# Sheet1.net
KiCad netlist of a schematic drawn in Altium Designer
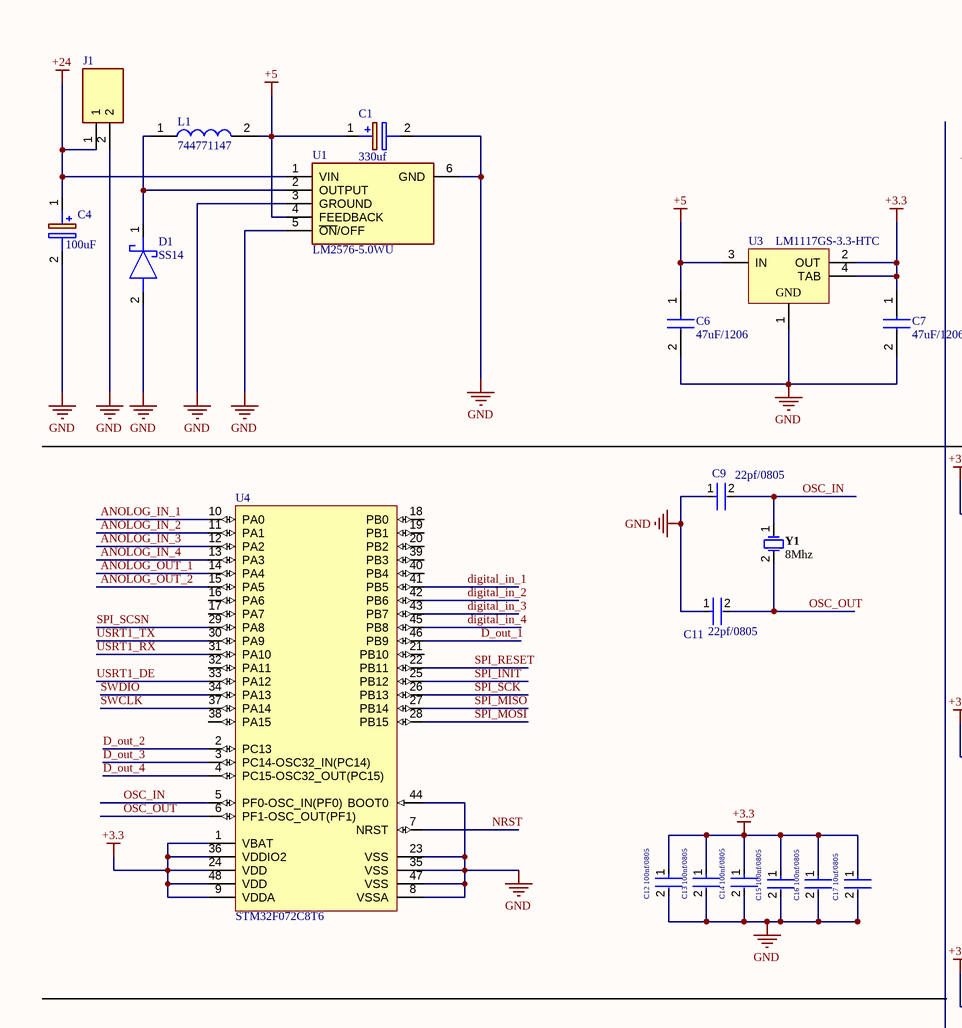
[diagram p0: Sheet1.SchDoc, top left]
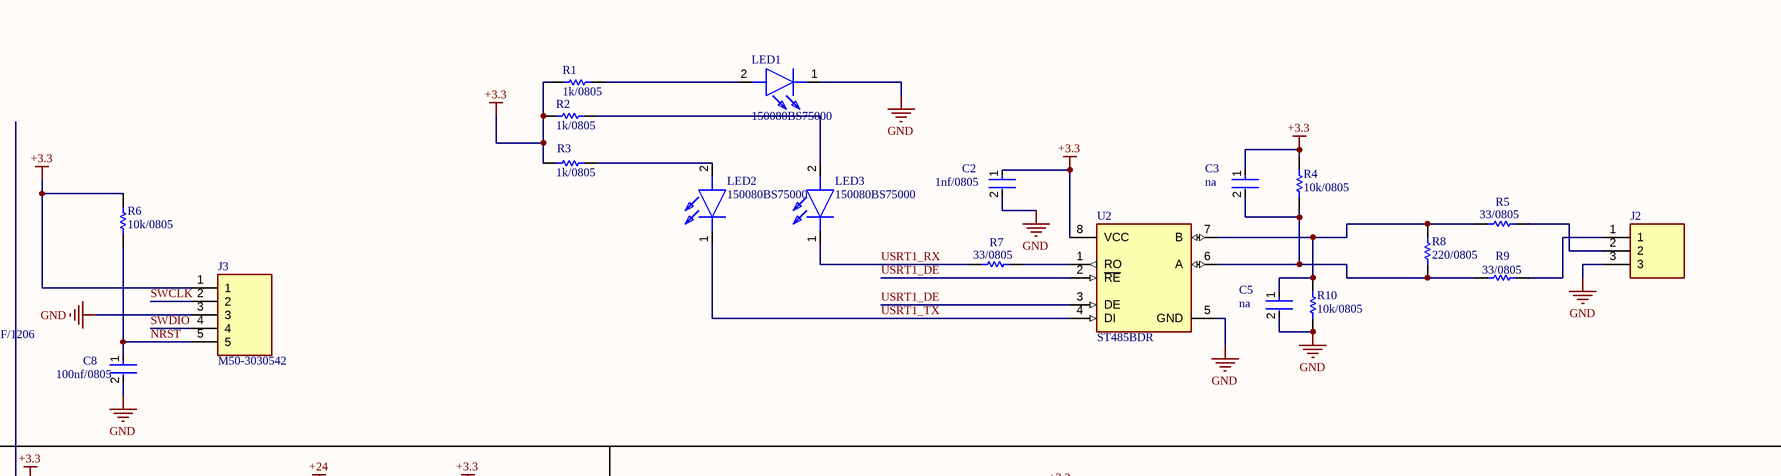
[diagram p1: Sheet1.SchDoc, top right]
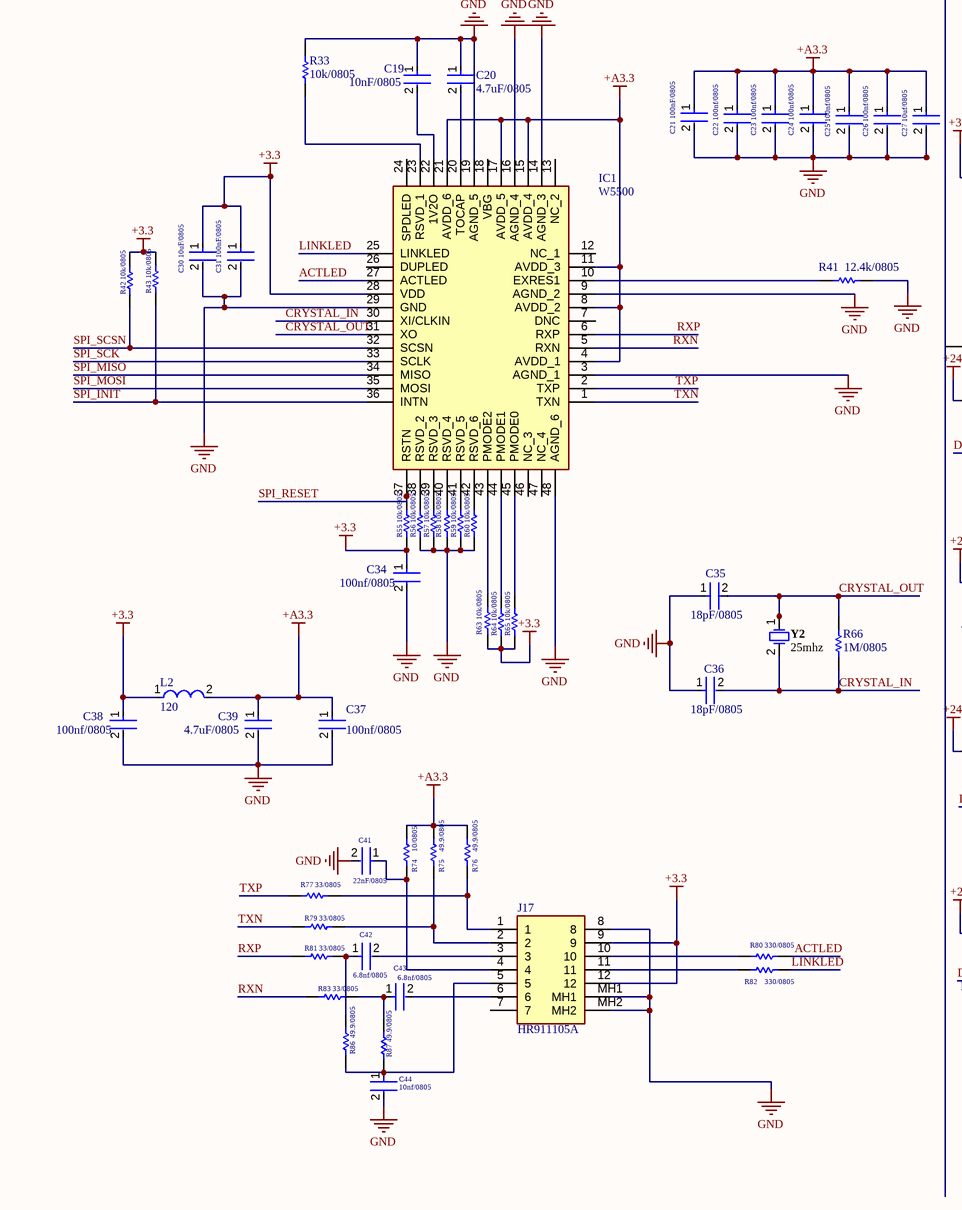
[diagram p2: Sheet1.SchDoc, bottom left]
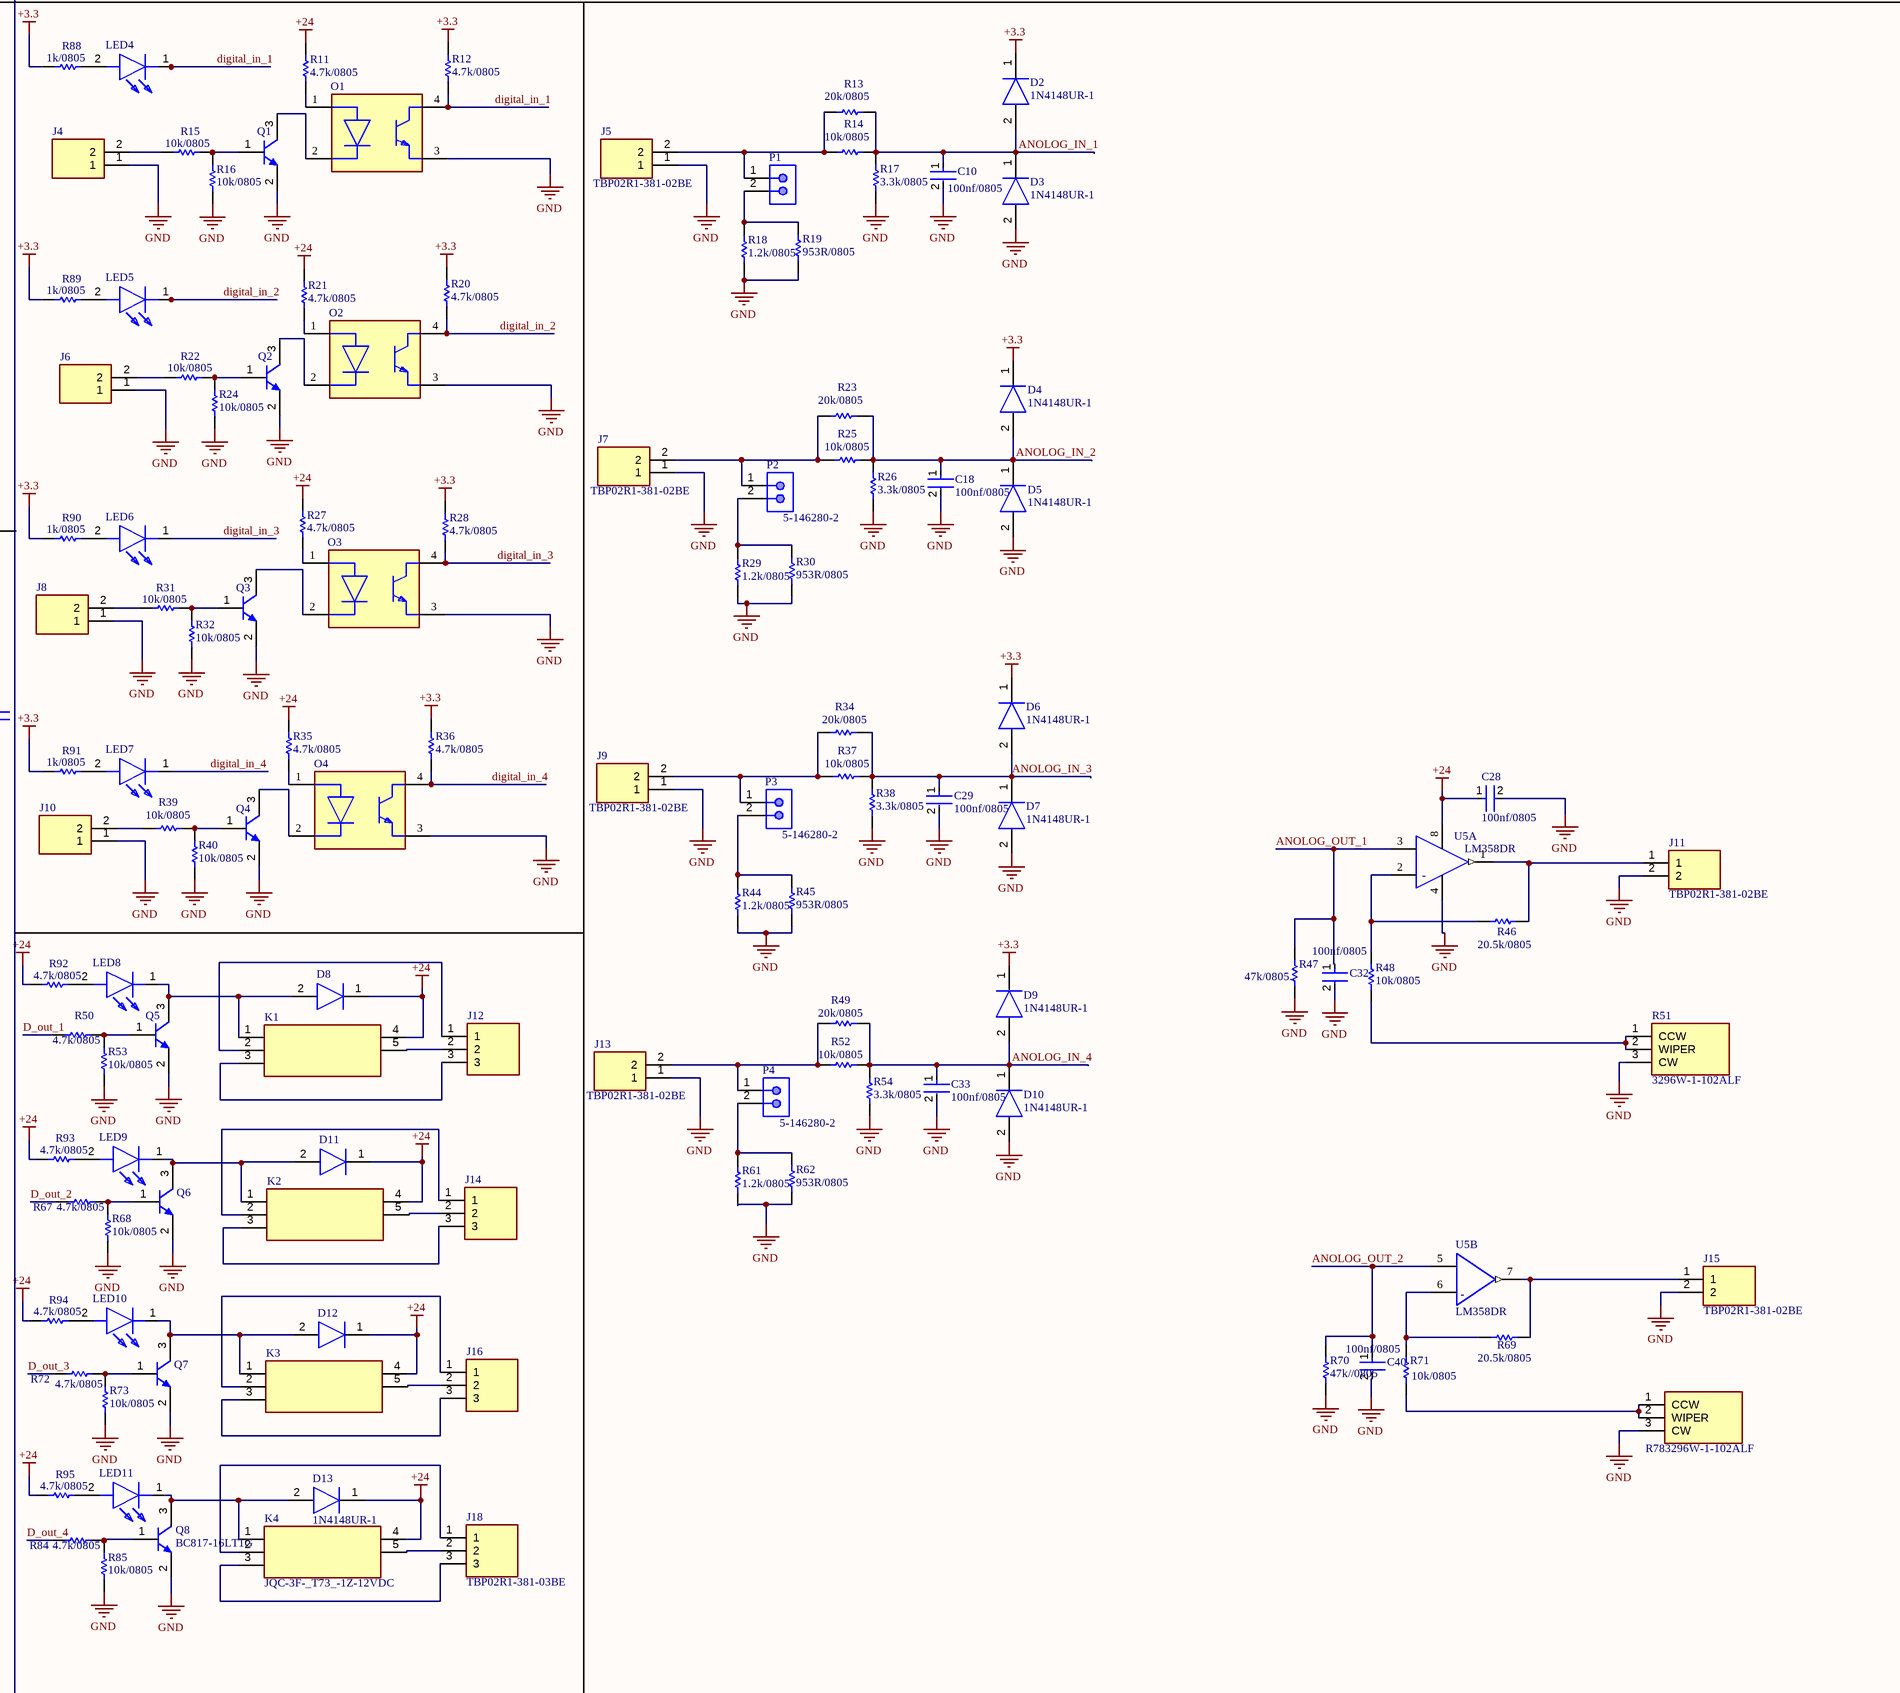
[diagram p3: Sheet1.SchDoc, bottom right]

(export (version "E")
  (design (tool "Eeschema 10.0.6"))
  (components
    (comp (ref "C1")
      (value "330uf")
      (footprint "SamacSys:CAPPRD500W60D1300H2700")
      (description "Capacitor Polarised")
      (fields
        (field (name "MANUFACTURER_PART_NUMBER") "ESH226M400AL4AA")
        (field (name "MOUSER PART NUMBER") "80-ESH226M400AL4AA")
      )
      (libsource (lib "") (part "ESH226M400AL4AA_1"))
    )
    (comp (ref "C2")
      (value "1nf/0805")
      (footprint "FP-C0805C-DG-MFG")
      (description "CAP CER 10UF 10V X5R 0805")
      (fields (field (name "TOLERANCE") "10%") (field (name "MANUFACTURER PART NUMBER") "C0805C106K8PACTU"))
      (libsource (lib "Altium Content Vault") (part "11868f565c42a9108669ba33697ecf6"))
    )
    (comp (ref "C3")
      (value "na")
      (footprint "FP-C0805C-DG-MFG")
      (description "CAP CER 10UF 10V X5R 0805")
      (fields (field (name "TOLERANCE") "10%") (field (name "MANUFACTURER PART NUMBER") "C0805C106K8PACTU"))
      (libsource (lib "Altium Content Vault") (part "11868f565c42a9108669ba33697ecf6"))
    )
    (comp (ref "C4")
      (value "100uF")
      (footprint "SamacSys:CAPPRD500W60D1300H2700")
      (description "Capacitor Polarised")
      (fields
        (field (name "MANUFACTURER_PART_NUMBER") "ESH226M400AL4AA")
        (field (name "MOUSER PART NUMBER") "80-ESH226M400AL4AA")
      )
      (libsource (lib "*") (part "ESH226M400AL4AA"))
    )
    (comp (ref "C5")
      (value "na")
      (footprint "FP-C0805C-DG-MFG")
      (description "CAP CER 10UF 10V X5R 0805")
      (fields (field (name "TOLERANCE") "10%") (field (name "MANUFACTURER PART NUMBER") "C0805C106K8PACTU"))
      (libsource (lib "Altium Content Vault") (part "11868f565c42a9108669ba33697ecf6"))
    )
    (comp (ref "C6")
      (value "47uF/1206")
      (footprint "SamacSys:CAPC3216X130N")
      (description "Capacitor")
      (fields
        (field (name "MANUFACTURER_PART_NUMBER") "CGA5H2C0G1H473J115AA")
        (field (name "MOUSER PART NUMBER") "810-CGA5H2C0G1H473J")
      )
      (libsource (lib "*") (part "CGA5H2C0G1H473J115AA"))
    )
    (comp (ref "C7")
      (value "47uF/1206")
      (footprint "SamacSys:CAPC3216X130N")
      (description "Capacitor")
      (fields
        (field (name "MANUFACTURER_PART_NUMBER") "CGA5H2C0G1H473J115AA")
        (field (name "MOUSER PART NUMBER") "810-CGA5H2C0G1H473J")
      )
      (libsource (lib "*") (part "CGA5H2C0G1H473J115AA"))
    )
    (comp (ref "C8")
      (value "100nf/0805")
      (footprint "FP-CL21-IPC_C")
      (description "CL21 Series 0805 3.3nF 25V ±5% Tolerance C0G Multilayer Ceramic Chip Capacitor")
      (fields (field (name "TOLERANCE") "5%"))
      (libsource (lib "Altium Content Vault") (part "b4654b650e69147ec39a6b967a45e02"))
    )
    (comp (ref "C9")
      (value "22pf/0805")
      (footprint "FP-CL21-IPC_A")
      (description "CL21 Series 0805 680nF 25V -20/+80% Tolerance Y5V Multilayer Ceramic Chip Capacitor")
      (fields (field (name "TOLERANCE") "80%"))
      (libsource (lib "Altium Content Vault") (part "b4654b650e69147ec39a6b967a45e02"))
    )
    (comp (ref "C10")
      (value "100nf/0805")
      (footprint "FP-CL21-IPC_C")
      (description "CL21 Series 0805 3.3nF 25V ±5% Tolerance C0G Multilayer Ceramic Chip Capacitor")
      (fields (field (name "TOLERANCE") "5%"))
      (libsource (lib "Altium Content Vault") (part "b4654b650e69147ec39a6b967a45e02"))
    )
    (comp (ref "C11")
      (value "22pf/0805")
      (footprint "FP-CL21-IPC_A")
      (description "CL21 Series 0805 680nF 25V -20/+80% Tolerance Y5V Multilayer Ceramic Chip Capacitor")
      (fields (field (name "TOLERANCE") "80%"))
      (libsource (lib "Altium Content Vault") (part "b4654b650e69147ec39a6b967a45e02"))
    )
    (comp (ref "C12")
      (value "100nf/0805")
      (footprint "FP-CL21-IPC_A")
      (description "CL21 Series 0805 680nF 25V -20/+80% Tolerance Y5V Multilayer Ceramic Chip Capacitor")
      (fields (field (name "TOLERANCE") "80%"))
      (libsource (lib "Altium Content Vault") (part "b4654b650e69147ec39a6b967a45e02"))
    )
    (comp (ref "C13")
      (value "100nf/0805")
      (footprint "FP-CL21-IPC_A")
      (description "CL21 Series 0805 680nF 25V -20/+80% Tolerance Y5V Multilayer Ceramic Chip Capacitor")
      (fields (field (name "TOLERANCE") "80%"))
      (libsource (lib "Altium Content Vault") (part "b4654b650e69147ec39a6b967a45e02"))
    )
    (comp (ref "C14")
      (value "100nf/0805")
      (footprint "FP-CL21-IPC_A")
      (description "CL21 Series 0805 680nF 25V -20/+80% Tolerance Y5V Multilayer Ceramic Chip Capacitor")
      (fields (field (name "TOLERANCE") "80%"))
      (libsource (lib "Altium Content Vault") (part "b4654b650e69147ec39a6b967a45e02"))
    )
    (comp (ref "C15")
      (value "100nf/0805")
      (footprint "FP-CL21-IPC_A")
      (description "CL21 Series 0805 680nF 25V -20/+80% Tolerance Y5V Multilayer Ceramic Chip Capacitor")
      (fields (field (name "TOLERANCE") "80%"))
      (libsource (lib "Altium Content Vault") (part "b4654b650e69147ec39a6b967a45e02"))
    )
    (comp (ref "C16")
      (value "100nf/0805")
      (footprint "FP-CL21-IPC_A")
      (description "CL21 Series 0805 680nF 25V -20/+80% Tolerance Y5V Multilayer Ceramic Chip Capacitor")
      (fields (field (name "TOLERANCE") "80%"))
      (libsource (lib "Altium Content Vault") (part "b4654b650e69147ec39a6b967a45e02"))
    )
    (comp (ref "C17")
      (value "10uf/0805")
      (footprint "FP-CL21-IPC_A")
      (description "CL21 Series 0805 680nF 25V -20/+80% Tolerance Y5V Multilayer Ceramic Chip Capacitor")
      (fields (field (name "TOLERANCE") "80%"))
      (libsource (lib "Altium Content Vault") (part "b4654b650e69147ec39a6b967a45e02"))
    )
    (comp (ref "C18")
      (value "100nf/0805")
      (footprint "FP-CL21-IPC_C")
      (description "CL21 Series 0805 3.3nF 25V ±5% Tolerance C0G Multilayer Ceramic Chip Capacitor")
      (fields (field (name "TOLERANCE") "5%"))
      (libsource (lib "Altium Content Vault") (part "b4654b650e69147ec39a6b967a45e02"))
    )
    (comp (ref "C19")
      (value "10nF/0805")
      (footprint "FP-CL21-IPC_A")
      (description "CL21 Series 0805 680nF 25V -20/+80% Tolerance Y5V Multilayer Ceramic Chip Capacitor")
      (fields (field (name "TOLERANCE") "80%"))
      (libsource (lib "Altium Content Vault") (part "b4654b650e69147ec39a6b967a45e02"))
    )
    (comp (ref "C20")
      (value "4.7uF/0805")
      (footprint "FP-CL21-IPC_A")
      (description "CL21 Series 0805 680nF 25V -20/+80% Tolerance Y5V Multilayer Ceramic Chip Capacitor")
      (fields (field (name "TOLERANCE") "80%"))
      (libsource (lib "Altium Content Vault") (part "b4654b650e69147ec39a6b967a45e02"))
    )
    (comp (ref "C21")
      (value "100nF/0805")
      (footprint "FP-CL21-IPC_A")
      (description "CL21 Series 0805 680nF 25V -20/+80% Tolerance Y5V Multilayer Ceramic Chip Capacitor")
      (fields (field (name "TOLERANCE") "80%"))
      (libsource (lib "Altium Content Vault") (part "b4654b650e69147ec39a6b967a45e02"))
    )
    (comp (ref "C22")
      (value "100nf/0805")
      (footprint "FP-CL21-IPC_A")
      (description "CL21 Series 0805 680nF 25V -20/+80% Tolerance Y5V Multilayer Ceramic Chip Capacitor")
      (fields (field (name "TOLERANCE") "80%"))
      (libsource (lib "Altium Content Vault") (part "b4654b650e69147ec39a6b967a45e02"))
    )
    (comp (ref "C23")
      (value "100nf/0805")
      (footprint "FP-CL21-IPC_A")
      (description "CL21 Series 0805 680nF 25V -20/+80% Tolerance Y5V Multilayer Ceramic Chip Capacitor")
      (fields (field (name "TOLERANCE") "80%"))
      (libsource (lib "Altium Content Vault") (part "b4654b650e69147ec39a6b967a45e02"))
    )
    (comp (ref "C24")
      (value "100nf/0805")
      (footprint "FP-CL21-IPC_A")
      (description "CL21 Series 0805 680nF 25V -20/+80% Tolerance Y5V Multilayer Ceramic Chip Capacitor")
      (fields (field (name "TOLERANCE") "80%"))
      (libsource (lib "Altium Content Vault") (part "b4654b650e69147ec39a6b967a45e02"))
    )
    (comp (ref "C25")
      (value "100nf/0805")
      (footprint "FP-CL21-IPC_A")
      (description "CL21 Series 0805 680nF 25V -20/+80% Tolerance Y5V Multilayer Ceramic Chip Capacitor")
      (fields (field (name "TOLERANCE") "80%"))
      (libsource (lib "Altium Content Vault") (part "b4654b650e69147ec39a6b967a45e02"))
    )
    (comp (ref "C26")
      (value "100nf/0805")
      (footprint "FP-CL21-IPC_A")
      (description "CL21 Series 0805 680nF 25V -20/+80% Tolerance Y5V Multilayer Ceramic Chip Capacitor")
      (fields (field (name "TOLERANCE") "80%"))
      (libsource (lib "Altium Content Vault") (part "b4654b650e69147ec39a6b967a45e02"))
    )
    (comp (ref "C27")
      (value "10uf/0805")
      (footprint "FP-CL21-IPC_A")
      (description "CL21 Series 0805 680nF 25V -20/+80% Tolerance Y5V Multilayer Ceramic Chip Capacitor")
      (fields (field (name "TOLERANCE") "80%"))
      (libsource (lib "Altium Content Vault") (part "b4654b650e69147ec39a6b967a45e02"))
    )
    (comp (ref "C28")
      (value "100nf/0805")
      (footprint "FP-CL21-IPC_C")
      (description "CL21 Series 0805 3.3nF 25V ±5% Tolerance C0G Multilayer Ceramic Chip Capacitor")
      (fields (field (name "TOLERANCE") "5%"))
      (libsource (lib "Altium Content Vault") (part "b4654b650e69147ec39a6b967a45e02"))
    )
    (comp (ref "C29")
      (value "100nf/0805")
      (footprint "FP-CL21-IPC_C")
      (description "CL21 Series 0805 3.3nF 25V ±5% Tolerance C0G Multilayer Ceramic Chip Capacitor")
      (fields (field (name "TOLERANCE") "5%"))
      (libsource (lib "Altium Content Vault") (part "b4654b650e69147ec39a6b967a45e02"))
    )
    (comp (ref "C30")
      (value "10uF/0805")
      (footprint "FP-CL21-IPC_A")
      (description "CL21 Series 0805 680nF 25V -20/+80% Tolerance Y5V Multilayer Ceramic Chip Capacitor")
      (fields (field (name "TOLERANCE") "80%"))
      (libsource (lib "Altium Content Vault") (part "b4654b650e69147ec39a6b967a45e02"))
    )
    (comp (ref "C31")
      (value "100nF/0805")
      (footprint "FP-CL21-IPC_A")
      (description "CL21 Series 0805 680nF 25V -20/+80% Tolerance Y5V Multilayer Ceramic Chip Capacitor")
      (fields (field (name "TOLERANCE") "80%"))
      (libsource (lib "Altium Content Vault") (part "b4654b650e69147ec39a6b967a45e02"))
    )
    (comp (ref "C32")
      (value "100nf/0805")
      (footprint "FP-CL21-IPC_C")
      (description "CL21 Series 0805 3.3nF 25V ±5% Tolerance C0G Multilayer Ceramic Chip Capacitor")
      (fields (field (name "TOLERANCE") "5%"))
      (libsource (lib "Altium Content Vault") (part "b4654b650e69147ec39a6b967a45e02"))
    )
    (comp (ref "C33")
      (value "100nf/0805")
      (footprint "FP-CL21-IPC_C")
      (description "CL21 Series 0805 3.3nF 25V ±5% Tolerance C0G Multilayer Ceramic Chip Capacitor")
      (fields (field (name "TOLERANCE") "5%"))
      (libsource (lib "Altium Content Vault") (part "b4654b650e69147ec39a6b967a45e02"))
    )
    (comp (ref "C34")
      (value "100nf/0805")
      (footprint "FP-CL21-IPC_C")
      (description "CL21 Series 0805 3.3nF 25V ±5% Tolerance C0G Multilayer Ceramic Chip Capacitor")
      (fields (field (name "TOLERANCE") "5%"))
      (libsource (lib "Altium Content Vault") (part "b4654b650e69147ec39a6b967a45e02"))
    )
    (comp (ref "C35")
      (value "18pF/0805")
      (footprint "FP-CL21-IPC_A")
      (description "CL21 Series 0805 680nF 25V -20/+80% Tolerance Y5V Multilayer Ceramic Chip Capacitor")
      (fields (field (name "TOLERANCE") "80%"))
      (libsource (lib "Altium Content Vault") (part "b4654b650e69147ec39a6b967a45e02"))
    )
    (comp (ref "C36")
      (value "18pF/0805")
      (footprint "FP-CL21-IPC_A")
      (description "CL21 Series 0805 680nF 25V -20/+80% Tolerance Y5V Multilayer Ceramic Chip Capacitor")
      (fields (field (name "TOLERANCE") "80%"))
      (libsource (lib "Altium Content Vault") (part "b4654b650e69147ec39a6b967a45e02"))
    )
    (comp (ref "C37")
      (value "100nf/0805")
      (footprint "FP-CL21-IPC_C")
      (description "CL21 Series 0805 3.3nF 25V ±5% Tolerance C0G Multilayer Ceramic Chip Capacitor")
      (fields (field (name "TOLERANCE") "5%"))
      (libsource (lib "Altium Content Vault") (part "b4654b650e69147ec39a6b967a45e02"))
    )
    (comp (ref "C38")
      (value "100nf/0805")
      (footprint "FP-CL21-IPC_C")
      (description "CL21 Series 0805 3.3nF 25V ±5% Tolerance C0G Multilayer Ceramic Chip Capacitor")
      (fields (field (name "TOLERANCE") "5%"))
      (libsource (lib "Altium Content Vault") (part "b4654b650e69147ec39a6b967a45e02"))
    )
    (comp (ref "C39")
      (value "4.7uF/0805")
      (footprint "FP-CL21-IPC_C")
      (description "CL21 Series 0805 3.3nF 25V ±5% Tolerance C0G Multilayer Ceramic Chip Capacitor")
      (fields (field (name "TOLERANCE") "5%"))
      (libsource (lib "Altium Content Vault") (part "b4654b650e69147ec39a6b967a45e02"))
    )
    (comp (ref "C40")
      (value "100nf/0805")
      (footprint "FP-CL21-IPC_C")
      (description "CL21 Series 0805 3.3nF 25V ±5% Tolerance C0G Multilayer Ceramic Chip Capacitor")
      (fields (field (name "TOLERANCE") "5%"))
      (libsource (lib "Altium Content Vault") (part "b4654b650e69147ec39a6b967a45e02"))
    )
    (comp (ref "C41")
      (value "22nF/0805")
      (footprint "FP-CL21-IPC_C")
      (description "CL21 Series 0805 3.3nF 25V ±5% Tolerance C0G Multilayer Ceramic Chip Capacitor")
      (fields (field (name "TOLERANCE") "5%"))
      (libsource (lib "Altium Content Vault") (part "b4654b650e69147ec39a6b967a45e02"))
    )
    (comp (ref "C42")
      (value "6.8nf/0805")
      (footprint "FP-CL21-IPC_C")
      (description "CL21 Series 0805 3.3nF 25V ±5% Tolerance C0G Multilayer Ceramic Chip Capacitor")
      (fields (field (name "TOLERANCE") "5%"))
      (libsource (lib "Altium Content Vault") (part "b4654b650e69147ec39a6b967a45e02"))
    )
    (comp (ref "C43")
      (value "6.8nf/0805")
      (footprint "FP-CL21-IPC_C")
      (description "CL21 Series 0805 3.3nF 25V ±5% Tolerance C0G Multilayer Ceramic Chip Capacitor")
      (fields (field (name "TOLERANCE") "5%"))
      (libsource (lib "Altium Content Vault") (part "b4654b650e69147ec39a6b967a45e02"))
    )
    (comp (ref "C44")
      (value "10nf/0805")
      (footprint "FP-CL21-IPC_C")
      (description "CL21 Series 0805 3.3nF 25V ±5% Tolerance C0G Multilayer Ceramic Chip Capacitor")
      (fields (field (name "TOLERANCE") "5%"))
      (libsource (lib "Altium Content Vault") (part "b4654b650e69147ec39a6b967a45e02"))
    )
    (comp (ref "D1")
      (value "SS14")
      (footprint "SamacSys:DIONM5327X242N")
      (description "Schottky Diode")
      (libsource (lib "*") (part "SS14"))
    )
    (comp (ref "D2")
      (value "1N4148UR-1")
      (footprint "SamacSys:1N4148UR1")
      (description "Diode")
      (fields (field (name "MOUSER PART NUMBER") "494-1N4148UR-1"))
      (libsource (lib "*") (part "1N4148UR-1"))
    )
    (comp (ref "D3")
      (value "1N4148UR-1")
      (footprint "SamacSys:1N4148UR1")
      (description "Diode")
      (fields (field (name "MOUSER PART NUMBER") "494-1N4148UR-1"))
      (libsource (lib "*") (part "1N4148UR-1"))
    )
    (comp (ref "D4")
      (value "1N4148UR-1")
      (footprint "SamacSys:1N4148UR1")
      (description "Diode")
      (fields (field (name "MOUSER PART NUMBER") "494-1N4148UR-1"))
      (libsource (lib "*") (part "1N4148UR-1"))
    )
    (comp (ref "D5")
      (value "1N4148UR-1")
      (footprint "SamacSys:1N4148UR1")
      (description "Diode")
      (fields (field (name "MOUSER PART NUMBER") "494-1N4148UR-1"))
      (libsource (lib "*") (part "1N4148UR-1"))
    )
    (comp (ref "D6")
      (value "1N4148UR-1")
      (footprint "SamacSys:1N4148UR1")
      (description "Diode")
      (fields (field (name "MOUSER PART NUMBER") "494-1N4148UR-1"))
      (libsource (lib "*") (part "1N4148UR-1"))
    )
    (comp (ref "D7")
      (value "1N4148UR-1")
      (footprint "SamacSys:1N4148UR1")
      (description "Diode")
      (fields (field (name "MOUSER PART NUMBER") "494-1N4148UR-1"))
      (libsource (lib "*") (part "1N4148UR-1"))
    )
    (comp (ref "D8")
      (value "~")
      (footprint "SamacSys:1N4148UR1")
      (description "Diode")
      (fields
        (field (name "MANUFACTURER_PART_NUMBER") "1N4148UR-1")
        (field (name "MOUSER PART NUMBER") "494-1N4148UR-1")
      )
      (libsource (lib "*") (part "1N4148UR-1"))
    )
    (comp (ref "D9")
      (value "1N4148UR-1")
      (footprint "SamacSys:1N4148UR1")
      (description "Diode")
      (fields (field (name "MOUSER PART NUMBER") "494-1N4148UR-1"))
      (libsource (lib "*") (part "1N4148UR-1"))
    )
    (comp (ref "D10")
      (value "1N4148UR-1")
      (footprint "SamacSys:1N4148UR1")
      (description "Diode")
      (fields (field (name "MOUSER PART NUMBER") "494-1N4148UR-1"))
      (libsource (lib "*") (part "1N4148UR-1"))
    )
    (comp (ref "D11")
      (value "~")
      (footprint "SamacSys:1N4148UR1")
      (description "Diode")
      (fields
        (field (name "MANUFACTURER_PART_NUMBER") "1N4148UR-1")
        (field (name "MOUSER PART NUMBER") "494-1N4148UR-1")
      )
      (libsource (lib "*") (part "1N4148UR-1"))
    )
    (comp (ref "D12")
      (value "~")
      (footprint "SamacSys:1N4148UR1")
      (description "Diode")
      (fields
        (field (name "MANUFACTURER_PART_NUMBER") "1N4148UR-1")
        (field (name "MOUSER PART NUMBER") "494-1N4148UR-1")
      )
      (libsource (lib "*") (part "1N4148UR-1"))
    )
    (comp (ref "D13")
      (value "1N4148UR-1")
      (footprint "SamacSys:1N4148UR1")
      (description "Diode")
      (fields (field (name "MOUSER PART NUMBER") "494-1N4148UR-1"))
      (libsource (lib "*") (part "1N4148UR-1"))
    )
    (comp (ref "IC1")
      (value "W5500")
      (footprint "SamacSys:QFP50P900X900X160-48N")
      (description "Integrated Circuit")
      (fields (field (name "MOUSER PART NUMBER") "950-W5500"))
      (libsource (lib "*") (part "W5500"))
    )
    (comp (ref "J1")
      (value "~")
      (footprint "SamacSys:TBP02R138102BE")
      (description "Connector")
      (fields
        (field (name "MANUFACTURER_PART_NUMBER") "TBP02R1-381-02BE")
        (field (name "MOUSER PART NUMBER") "490-TBP02R1-381-02BE")
      )
      (libsource (lib "") (part "TBP02R1-381-02BE_1"))
    )
    (comp (ref "J2")
      (value "~")
      (footprint "SamacSys:TBP02R138103BE")
      (description "Connector")
      (fields
        (field (name "MANUFACTURER_PART_NUMBER") "TBP02R1-381-03BE")
        (field (name "MOUSER PART NUMBER") "490-TBP02R1-381-03BE")
      )
      (libsource (lib "*") (part "TBP02R1-381-03BE"))
    )
    (comp (ref "J3")
      (value "M50-3030542")
      (footprint "SamacSys:M503030542")
      (description "Connector")
      (fields (field (name "MOUSER PART NUMBER") "855-M50-3030542"))
      (libsource (lib "*") (part "M50-3030542"))
    )
    (comp (ref "J4")
      (value "~")
      (footprint "SamacSys:TBP02R138102BE")
      (description "Connector")
      (fields
        (field (name "MANUFACTURER_PART_NUMBER") "TBP02R1-381-02BE")
        (field (name "MOUSER PART NUMBER") "490-TBP02R1-381-02BE")
      )
      (libsource (lib "*") (part "TBP02R1-381-02BE"))
    )
    (comp (ref "J5")
      (value "TBP02R1-381-02BE")
      (footprint "SamacSys:TBP02R138102BE")
      (description "Connector")
      (fields (field (name "MOUSER PART NUMBER") "490-TBP02R1-381-02BE"))
      (libsource (lib "*") (part "TBP02R1-381-02BE"))
    )
    (comp (ref "J6")
      (value "~")
      (footprint "SamacSys:TBP02R138102BE")
      (description "Connector")
      (fields
        (field (name "MANUFACTURER_PART_NUMBER") "TBP02R1-381-02BE")
        (field (name "MOUSER PART NUMBER") "490-TBP02R1-381-02BE")
      )
      (libsource (lib "*") (part "TBP02R1-381-02BE"))
    )
    (comp (ref "J7")
      (value "TBP02R1-381-02BE")
      (footprint "SamacSys:TBP02R138102BE")
      (description "Connector")
      (fields (field (name "MOUSER PART NUMBER") "490-TBP02R1-381-02BE"))
      (libsource (lib "*") (part "TBP02R1-381-02BE"))
    )
    (comp (ref "J8")
      (value "~")
      (footprint "SamacSys:TBP02R138102BE")
      (description "Connector")
      (fields
        (field (name "MANUFACTURER_PART_NUMBER") "TBP02R1-381-02BE")
        (field (name "MOUSER PART NUMBER") "490-TBP02R1-381-02BE")
      )
      (libsource (lib "*") (part "TBP02R1-381-02BE"))
    )
    (comp (ref "J9")
      (value "TBP02R1-381-02BE")
      (footprint "SamacSys:TBP02R138102BE")
      (description "Connector")
      (fields (field (name "MOUSER PART NUMBER") "490-TBP02R1-381-02BE"))
      (libsource (lib "*") (part "TBP02R1-381-02BE"))
    )
    (comp (ref "J10")
      (value "~")
      (footprint "SamacSys:TBP02R138102BE")
      (description "Connector")
      (fields
        (field (name "MANUFACTURER_PART_NUMBER") "TBP02R1-381-02BE")
        (field (name "MOUSER PART NUMBER") "490-TBP02R1-381-02BE")
      )
      (libsource (lib "*") (part "TBP02R1-381-02BE"))
    )
    (comp (ref "J11")
      (value "TBP02R1-381-02BE")
      (footprint "SamacSys:TBP02R138102BE")
      (description "Connector")
      (fields (field (name "MOUSER PART NUMBER") "490-TBP02R1-381-02BE"))
      (libsource (lib "") (part "TBP02R1-381-02BE_2"))
    )
    (comp (ref "J12")
      (value "~")
      (footprint "SamacSys:TBP02R138103BE")
      (description "Connector")
      (fields
        (field (name "MANUFACTURER_PART_NUMBER") "TBP02R1-381-03BE")
        (field (name "MOUSER PART NUMBER") "490-TBP02R1-381-03BE")
      )
      (libsource (lib "*") (part "TBP02R1-381-03BE"))
    )
    (comp (ref "J13")
      (value "TBP02R1-381-02BE")
      (footprint "SamacSys:TBP02R138102BE")
      (description "Connector")
      (fields (field (name "MOUSER PART NUMBER") "490-TBP02R1-381-02BE"))
      (libsource (lib "*") (part "TBP02R1-381-02BE"))
    )
    (comp (ref "J14")
      (value "~")
      (footprint "SamacSys:TBP02R138103BE")
      (description "Connector")
      (fields
        (field (name "MANUFACTURER_PART_NUMBER") "TBP02R1-381-03BE")
        (field (name "MOUSER PART NUMBER") "490-TBP02R1-381-03BE")
      )
      (libsource (lib "*") (part "TBP02R1-381-03BE"))
    )
    (comp (ref "J15")
      (value "TBP02R1-381-02BE")
      (footprint "SamacSys:TBP02R138102BE")
      (description "Connector")
      (fields (field (name "MOUSER PART NUMBER") "490-TBP02R1-381-02BE"))
      (libsource (lib "") (part "TBP02R1-381-02BE_2"))
    )
    (comp (ref "J16")
      (value "~")
      (footprint "SamacSys:TBP02R138103BE")
      (description "Connector")
      (fields
        (field (name "MANUFACTURER_PART_NUMBER") "TBP02R1-381-03BE")
        (field (name "MOUSER PART NUMBER") "490-TBP02R1-381-03BE")
      )
      (libsource (lib "*") (part "TBP02R1-381-03BE"))
    )
    (comp (ref "J17")
      (value "HR911105A")
      (footprint "SamacSys:HR911105A")
      (description "Connector")
      (libsource (lib "*") (part "HR911105A"))
    )
    (comp (ref "J18")
      (value "TBP02R1-381-03BE")
      (footprint "SamacSys:TBP02R138103BE")
      (description "Connector")
      (fields (field (name "MOUSER PART NUMBER") "490-TBP02R1-381-03BE"))
      (libsource (lib "*") (part "TBP02R1-381-03BE"))
    )
    (comp (ref "K1")
      (value "~")
      (footprint "SamacSys:JQC3FT731Z12VDC")
      (description "Relay or Contactor")
      (fields (field (name "MANUFACTURER_PART_NUMBER") "JQC-3F-(T73)-1Z-12VDC"))
      (libsource (lib "*") (part "JQC-3F-_T73_-1Z-12VDC"))
    )
    (comp (ref "K2")
      (value "~")
      (footprint "SamacSys:JQC3FT731Z12VDC")
      (description "Relay or Contactor")
      (fields (field (name "MANUFACTURER_PART_NUMBER") "JQC-3F-(T73)-1Z-12VDC"))
      (libsource (lib "*") (part "JQC-3F-_T73_-1Z-12VDC"))
    )
    (comp (ref "K3")
      (value "~")
      (footprint "SamacSys:JQC3FT731Z12VDC")
      (description "Relay or Contactor")
      (fields (field (name "MANUFACTURER_PART_NUMBER") "JQC-3F-(T73)-1Z-12VDC"))
      (libsource (lib "*") (part "JQC-3F-_T73_-1Z-12VDC"))
    )
    (comp (ref "K4")
      (value "JQC-3F-_T73_-1Z-12VDC")
      (footprint "SamacSys:JQC3FT731Z12VDC")
      (description "Relay or Contactor")
      (fields (field (name "MANUFACTURER_PART_NUMBER") "JQC-3F-(T73)-1Z-12VDC"))
      (libsource (lib "*") (part "JQC-3F-_T73_-1Z-12VDC"))
    )
    (comp (ref "L1")
      (value "744771147")
      (footprint "SamacSys:INDPM120120X600N")
      (description "Inductor")
      (fields (field (name "MOUSER PART NUMBER") "710-744771147"))
      (libsource (lib "*") (part "744771147"))
    )
    (comp (ref "L2")
      (value "120")
      (footprint "FP-LQH31CN_03-MFG")
      (description "Wire Wound Ferrite Inductor for General Circuits 56μH ±10% 11.57Ω 50mA 1206")
      (fields (field (name "TOLERANCE") "10%"))
      (libsource (lib "Altium Content Vault") (part "725321dda6339637d4d059423bc1c3c"))
    )
    (comp (ref "LED1")
      (value "150080BS75000")
      (footprint "SamacSys:LEDC2012X80N")
      (description "LED")
      (fields (field (name "MOUSER PART NUMBER") "710-150080BS75000"))
      (libsource (lib "*") (part "150080BS75000"))
    )
    (comp (ref "LED2")
      (value "150080BS75000")
      (footprint "SamacSys:LEDC2012X80N")
      (description "LED")
      (fields (field (name "MOUSER PART NUMBER") "710-150080BS75000"))
      (libsource (lib "*") (part "150080BS75000"))
    )
    (comp (ref "LED3")
      (value "150080BS75000")
      (footprint "SamacSys:LEDC2012X80N")
      (description "LED")
      (fields (field (name "MOUSER PART NUMBER") "710-150080BS75000"))
      (libsource (lib "*") (part "150080BS75000"))
    )
    (comp (ref "LED4")
      (value "~")
      (footprint "SamacSys:LEDC2012X80N")
      (description "LED")
      (fields
        (field (name "MANUFACTURER_PART_NUMBER") "150080BS75000")
        (field (name "MOUSER PART NUMBER") "710-150080BS75000")
      )
      (libsource (lib "*") (part "150080BS75000"))
    )
    (comp (ref "LED5")
      (value "~")
      (footprint "SamacSys:LEDC2012X80N")
      (description "LED")
      (fields
        (field (name "MANUFACTURER_PART_NUMBER") "150080BS75000")
        (field (name "MOUSER PART NUMBER") "710-150080BS75000")
      )
      (libsource (lib "*") (part "150080BS75000"))
    )
    (comp (ref "LED6")
      (value "~")
      (footprint "SamacSys:LEDC2012X80N")
      (description "LED")
      (fields
        (field (name "MANUFACTURER_PART_NUMBER") "150080BS75000")
        (field (name "MOUSER PART NUMBER") "710-150080BS75000")
      )
      (libsource (lib "*") (part "150080BS75000"))
    )
    (comp (ref "LED7")
      (value "~")
      (footprint "SamacSys:LEDC2012X80N")
      (description "LED")
      (fields
        (field (name "MANUFACTURER_PART_NUMBER") "150080BS75000")
        (field (name "MOUSER PART NUMBER") "710-150080BS75000")
      )
      (libsource (lib "*") (part "150080BS75000"))
    )
    (comp (ref "LED8")
      (value "~")
      (footprint "SamacSys:LEDC2012X80N")
      (description "LED")
      (fields
        (field (name "MANUFACTURER_PART_NUMBER") "150080BS75000")
        (field (name "MOUSER PART NUMBER") "710-150080BS75000")
      )
      (libsource (lib "*") (part "150080BS75000"))
    )
    (comp (ref "LED9")
      (value "~")
      (footprint "SamacSys:LEDC2012X80N")
      (description "LED")
      (fields
        (field (name "MANUFACTURER_PART_NUMBER") "150080BS75000")
        (field (name "MOUSER PART NUMBER") "710-150080BS75000")
      )
      (libsource (lib "*") (part "150080BS75000"))
    )
    (comp (ref "LED10")
      (value "~")
      (footprint "SamacSys:LEDC2012X80N")
      (description "LED")
      (fields
        (field (name "MANUFACTURER_PART_NUMBER") "150080BS75000")
        (field (name "MOUSER PART NUMBER") "710-150080BS75000")
      )
      (libsource (lib "*") (part "150080BS75000"))
    )
    (comp (ref "LED11")
      (value "~")
      (footprint "SamacSys:LEDC2012X80N")
      (description "LED")
      (fields
        (field (name "MANUFACTURER_PART_NUMBER") "150080BS75000")
        (field (name "MOUSER PART NUMBER") "710-150080BS75000")
      )
      (libsource (lib "*") (part "150080BS75000"))
    )
    (comp (ref "O1")
      (value "~")
      (footprint "FP-PC817XNNIP0F-MFG")
      (description "OPTOISOLATOR 5KV TRANS 4SMD")
      (libsource (lib "Altium Content Vault") (part "6470904bf6395c62928ee73e60120b8"))
    )
    (comp (ref "O2")
      (value "~")
      (footprint "FP-PC817XNNIP0F-MFG")
      (description "OPTOISOLATOR 5KV TRANS 4SMD")
      (libsource (lib "Altium Content Vault") (part "6470904bf6395c62928ee73e60120b8"))
    )
    (comp (ref "O3")
      (value "~")
      (footprint "FP-PC817XNNIP0F-MFG")
      (description "OPTOISOLATOR 5KV TRANS 4SMD")
      (libsource (lib "Altium Content Vault") (part "6470904bf6395c62928ee73e60120b8"))
    )
    (comp (ref "O4")
      (value "~")
      (footprint "FP-PC817XNNIP0F-MFG")
      (description "OPTOISOLATOR 5KV TRANS 4SMD")
      (libsource (lib "Altium Content Vault") (part "6470904bf6395c62928ee73e60120b8"))
    )
    (comp (ref "P1")
      (value "~")
      (footprint "TECO-5-146280-2_V")
      (fields (field (name "MANUFACTURER") "TE Connectivity"))
      (libsource (lib "Altium Content Vault") (part "CN-1P-M-R2"))
    )
    (comp (ref "P2")
      (value "5-146280-2")
      (footprint "TECO-5-146280-2_V")
      (fields (field (name "MANUFACTURER") "TE Connectivity"))
      (libsource (lib "Altium Content Vault") (part "CN-1P-M-R2"))
    )
    (comp (ref "P3")
      (value "5-146280-2")
      (footprint "TECO-5-146280-2_V")
      (fields (field (name "MANUFACTURER") "TE Connectivity"))
      (libsource (lib "Altium Content Vault") (part "CN-1P-M-R2"))
    )
    (comp (ref "P4")
      (value "5-146280-2")
      (footprint "TECO-5-146280-2_V")
      (fields (field (name "MANUFACTURER") "TE Connectivity"))
      (libsource (lib "Altium Content Vault") (part "CN-1P-M-R2"))
    )
    (comp (ref "Q1")
      (value "~")
      (footprint "ONSC-SOT-23-3-318-08_V")
      (description "General Purpose Transistor, NPN Silicon, 3-Pin SOT-23, Pb-Free, Tape and Reel")
      (fields (field (name "PARTNUMBER") "BC817-16LT1G") (field (name "MANUFACTURER") "On Semiconductor"))
      (libsource (lib "Altium Content Vault") (part "ONSC-NPN-B1E2C3-3"))
    )
    (comp (ref "Q2")
      (value "~")
      (footprint "ONSC-SOT-23-3-318-08_V")
      (description "General Purpose Transistor, NPN Silicon, 3-Pin SOT-23, Pb-Free, Tape and Reel")
      (fields (field (name "PARTNUMBER") "BC817-16LT1G") (field (name "MANUFACTURER") "On Semiconductor"))
      (libsource (lib "Altium Content Vault") (part "ONSC-NPN-B1E2C3-3"))
    )
    (comp (ref "Q3")
      (value "~")
      (footprint "ONSC-SOT-23-3-318-08_V")
      (description "General Purpose Transistor, NPN Silicon, 3-Pin SOT-23, Pb-Free, Tape and Reel")
      (fields (field (name "PARTNUMBER") "BC817-16LT1G") (field (name "MANUFACTURER") "On Semiconductor"))
      (libsource (lib "Altium Content Vault") (part "ONSC-NPN-B1E2C3-3"))
    )
    (comp (ref "Q4")
      (value "~")
      (footprint "ONSC-SOT-23-3-318-08_V")
      (description "General Purpose Transistor, NPN Silicon, 3-Pin SOT-23, Pb-Free, Tape and Reel")
      (fields (field (name "PARTNUMBER") "BC817-16LT1G") (field (name "MANUFACTURER") "On Semiconductor"))
      (libsource (lib "Altium Content Vault") (part "ONSC-NPN-B1E2C3-3"))
    )
    (comp (ref "Q5")
      (value "~")
      (footprint "ONSC-SOT-23-3-318-08_V")
      (description "General Purpose Transistor, NPN Silicon, 3-Pin SOT-23, Pb-Free, Tape and Reel")
      (fields (field (name "PARTNUMBER") "BC817-16LT1G") (field (name "MANUFACTURER") "On Semiconductor"))
      (libsource (lib "Altium Content Vault") (part "ONSC-NPN-B1E2C3-3"))
    )
    (comp (ref "Q6")
      (value "~")
      (footprint "ONSC-SOT-23-3-318-08_V")
      (description "General Purpose Transistor, NPN Silicon, 3-Pin SOT-23, Pb-Free, Tape and Reel")
      (fields (field (name "PARTNUMBER") "BC817-16LT1G") (field (name "MANUFACTURER") "On Semiconductor"))
      (libsource (lib "Altium Content Vault") (part "ONSC-NPN-B1E2C3-3"))
    )
    (comp (ref "Q7")
      (value "~")
      (footprint "ONSC-SOT-23-3-318-08_V")
      (description "General Purpose Transistor, NPN Silicon, 3-Pin SOT-23, Pb-Free, Tape and Reel")
      (fields (field (name "PARTNUMBER") "BC817-16LT1G") (field (name "MANUFACTURER") "On Semiconductor"))
      (libsource (lib "Altium Content Vault") (part "ONSC-NPN-B1E2C3-3"))
    )
    (comp (ref "Q8")
      (value "BC817-16LT1G")
      (footprint "ONSC-SOT-23-3-318-08_V")
      (description "General Purpose Transistor, NPN Silicon, 3-Pin SOT-23, Pb-Free, Tape and Reel")
      (fields (field (name "MANUFACTURER") "On Semiconductor"))
      (libsource (lib "Altium Content Vault") (part "ONSC-NPN-B1E2C3-3"))
    )
    (comp (ref "R1")
      (value "1k/0805")
      (footprint "RESC2013X50X30ML20T20")
      (fields (field (name "PART NUMBER") "CRCW0805270RFKEA") (field (name "MANUFACTURER") "Vishay Dale"))
      (libsource (lib "Altium Content Vault") (part "RES"))
    )
    (comp (ref "R2")
      (value "1k/0805")
      (footprint "RESC2013X50X30ML20T20")
      (fields (field (name "PART NUMBER") "CRCW0805270RFKEA") (field (name "MANUFACTURER") "Vishay Dale"))
      (libsource (lib "Altium Content Vault") (part "RES"))
    )
    (comp (ref "R3")
      (value "1k/0805")
      (footprint "RESC2013X50X30ML20T20")
      (fields (field (name "PART NUMBER") "CRCW0805270RFKEA") (field (name "MANUFACTURER") "Vishay Dale"))
      (libsource (lib "Altium Content Vault") (part "RES"))
    )
    (comp (ref "R4")
      (value "10k/0805")
      (footprint "RESC2013X50X30ML20T20")
      (fields (field (name "PART NUMBER") "CRCW0805270RFKEA") (field (name "MANUFACTURER") "Vishay Dale"))
      (libsource (lib "Altium Content Vault") (part "RES"))
    )
    (comp (ref "R5")
      (value "33/0805")
      (footprint "RESC2013X50X30ML20T20")
      (fields (field (name "PART NUMBER") "CRCW0805270RFKEA") (field (name "MANUFACTURER") "Vishay Dale"))
      (libsource (lib "Altium Content Vault") (part "RES"))
    )
    (comp (ref "R6")
      (value "10k/0805")
      (footprint "RESC2013X50X30ML20T20")
      (fields (field (name "PART NUMBER") "CRCW0805270RFKEA") (field (name "MANUFACTURER") "Vishay Dale"))
      (libsource (lib "Altium Content Vault") (part "RES"))
    )
    (comp (ref "R7")
      (value "33/0805")
      (footprint "RESC2013X50X30ML20T20")
      (fields (field (name "PART NUMBER") "CRCW0805270RFKEA") (field (name "MANUFACTURER") "Vishay Dale"))
      (libsource (lib "Altium Content Vault") (part "RES"))
    )
    (comp (ref "R8")
      (value "220/0805")
      (footprint "RESC2013X50X30ML20T20")
      (fields (field (name "PART NUMBER") "CRCW0805270RFKEA") (field (name "MANUFACTURER") "Vishay Dale"))
      (libsource (lib "Altium Content Vault") (part "RES"))
    )
    (comp (ref "R9")
      (value "33/0805")
      (footprint "RESC2013X50X30ML20T20")
      (fields (field (name "PART NUMBER") "CRCW0805270RFKEA") (field (name "MANUFACTURER") "Vishay Dale"))
      (libsource (lib "Altium Content Vault") (part "RES"))
    )
    (comp (ref "R10")
      (value "10k/0805")
      (footprint "RESC2013X50X30ML20T20")
      (fields (field (name "PART NUMBER") "CRCW0805270RFKEA") (field (name "MANUFACTURER") "Vishay Dale"))
      (libsource (lib "Altium Content Vault") (part "RES"))
    )
    (comp (ref "R11")
      (value "4.7k/0805")
      (footprint "RESC2013X50X30ML20T20")
      (fields (field (name "PART NUMBER") "CRCW0805270RFKEA") (field (name "MANUFACTURER") "Vishay Dale"))
      (libsource (lib "Altium Content Vault") (part "RES"))
    )
    (comp (ref "R12")
      (value "4.7k/0805")
      (footprint "RESC2013X50X30ML20T20")
      (fields (field (name "PART NUMBER") "CRCW0805270RFKEA") (field (name "MANUFACTURER") "Vishay Dale"))
      (libsource (lib "Altium Content Vault") (part "RES"))
    )
    (comp (ref "R13")
      (value "20k/0805")
      (footprint "RESC2013X50X30ML20T20")
      (fields (field (name "PART NUMBER") "CRCW0805270RFKEA") (field (name "MANUFACTURER") "Vishay Dale"))
      (libsource (lib "Altium Content Vault") (part "RES"))
    )
    (comp (ref "R14")
      (value "10k/0805")
      (footprint "RESC2013X50X30ML20T20")
      (fields (field (name "PART NUMBER") "CRCW0805270RFKEA") (field (name "MANUFACTURER") "Vishay Dale"))
      (libsource (lib "Altium Content Vault") (part "RES"))
    )
    (comp (ref "R15")
      (value "10k/0805")
      (footprint "RESC2013X50X30ML20T20")
      (fields (field (name "PART NUMBER") "CRCW0805270RFKEA") (field (name "MANUFACTURER") "Vishay Dale"))
      (libsource (lib "Altium Content Vault") (part "RES"))
    )
    (comp (ref "R16")
      (value "10k/0805")
      (footprint "RESC2013X50X30ML20T20")
      (fields (field (name "PART NUMBER") "CRCW0805270RFKEA") (field (name "MANUFACTURER") "Vishay Dale"))
      (libsource (lib "Altium Content Vault") (part "RES"))
    )
    (comp (ref "R17")
      (value "3.3k/0805")
      (footprint "RESC2013X50X30ML20T20")
      (fields (field (name "PART NUMBER") "CRCW0805270RFKEA") (field (name "MANUFACTURER") "Vishay Dale"))
      (libsource (lib "Altium Content Vault") (part "RES"))
    )
    (comp (ref "R18")
      (value "1.2k/0805")
      (footprint "RESC2013X50X30ML20T20")
      (fields (field (name "PART NUMBER") "CRCW0805270RFKEA") (field (name "MANUFACTURER") "Vishay Dale"))
      (libsource (lib "Altium Content Vault") (part "RES"))
    )
    (comp (ref "R19")
      (value "953R/0805")
      (footprint "RESC2013X50X30ML20T20")
      (fields (field (name "PART NUMBER") "CRCW0805270RFKEA") (field (name "MANUFACTURER") "Vishay Dale"))
      (libsource (lib "Altium Content Vault") (part "RES"))
    )
    (comp (ref "R20")
      (value "4.7k/0805")
      (footprint "RESC2013X50X30ML20T20")
      (fields (field (name "PART NUMBER") "CRCW0805270RFKEA") (field (name "MANUFACTURER") "Vishay Dale"))
      (libsource (lib "Altium Content Vault") (part "RES"))
    )
    (comp (ref "R21")
      (value "4.7k/0805")
      (footprint "RESC2013X50X30ML20T20")
      (fields (field (name "PART NUMBER") "CRCW0805270RFKEA") (field (name "MANUFACTURER") "Vishay Dale"))
      (libsource (lib "Altium Content Vault") (part "RES"))
    )
    (comp (ref "R22")
      (value "10k/0805")
      (footprint "RESC2013X50X30ML20T20")
      (fields (field (name "PART NUMBER") "CRCW0805270RFKEA") (field (name "MANUFACTURER") "Vishay Dale"))
      (libsource (lib "Altium Content Vault") (part "RES"))
    )
    (comp (ref "R23")
      (value "20k/0805")
      (footprint "RESC2013X50X30ML20T20")
      (fields (field (name "PART NUMBER") "CRCW0805270RFKEA") (field (name "MANUFACTURER") "Vishay Dale"))
      (libsource (lib "Altium Content Vault") (part "RES"))
    )
    (comp (ref "R24")
      (value "10k/0805")
      (footprint "RESC2013X50X30ML20T20")
      (fields (field (name "PART NUMBER") "CRCW0805270RFKEA") (field (name "MANUFACTURER") "Vishay Dale"))
      (libsource (lib "Altium Content Vault") (part "RES"))
    )
    (comp (ref "R25")
      (value "10k/0805")
      (footprint "RESC2013X50X30ML20T20")
      (fields (field (name "PART NUMBER") "CRCW0805270RFKEA") (field (name "MANUFACTURER") "Vishay Dale"))
      (libsource (lib "Altium Content Vault") (part "RES"))
    )
    (comp (ref "R26")
      (value "3.3k/0805")
      (footprint "RESC2013X50X30ML20T20")
      (fields (field (name "PART NUMBER") "CRCW0805270RFKEA") (field (name "MANUFACTURER") "Vishay Dale"))
      (libsource (lib "Altium Content Vault") (part "RES"))
    )
    (comp (ref "R27")
      (value "4.7k/0805")
      (footprint "RESC2013X50X30ML20T20")
      (fields (field (name "PART NUMBER") "CRCW0805270RFKEA") (field (name "MANUFACTURER") "Vishay Dale"))
      (libsource (lib "Altium Content Vault") (part "RES"))
    )
    (comp (ref "R28")
      (value "4.7k/0805")
      (footprint "RESC2013X50X30ML20T20")
      (fields (field (name "PART NUMBER") "CRCW0805270RFKEA") (field (name "MANUFACTURER") "Vishay Dale"))
      (libsource (lib "Altium Content Vault") (part "RES"))
    )
    (comp (ref "R29")
      (value "1.2k/0805")
      (footprint "RESC2013X50X30ML20T20")
      (fields (field (name "PART NUMBER") "CRCW0805270RFKEA") (field (name "MANUFACTURER") "Vishay Dale"))
      (libsource (lib "Altium Content Vault") (part "RES"))
    )
    (comp (ref "R30")
      (value "953R/0805")
      (footprint "RESC2013X50X30ML20T20")
      (fields (field (name "PART NUMBER") "CRCW0805270RFKEA") (field (name "MANUFACTURER") "Vishay Dale"))
      (libsource (lib "Altium Content Vault") (part "RES"))
    )
    (comp (ref "R31")
      (value "10k/0805")
      (footprint "RESC2013X50X30ML20T20")
      (fields (field (name "PART NUMBER") "CRCW0805270RFKEA") (field (name "MANUFACTURER") "Vishay Dale"))
      (libsource (lib "Altium Content Vault") (part "RES"))
    )
    (comp (ref "R32")
      (value "10k/0805")
      (footprint "RESC2013X50X30ML20T20")
      (fields (field (name "PART NUMBER") "CRCW0805270RFKEA") (field (name "MANUFACTURER") "Vishay Dale"))
      (libsource (lib "Altium Content Vault") (part "RES"))
    )
    (comp (ref "R33")
      (value "10k/0805")
      (footprint "RESC2013X50X30ML20T20")
      (fields (field (name "PART NUMBER") "CRCW0805270RFKEA") (field (name "MANUFACTURER") "Vishay Dale"))
      (libsource (lib "Altium Content Vault") (part "RES"))
    )
    (comp (ref "R34")
      (value "20k/0805")
      (footprint "RESC2013X50X30ML20T20")
      (fields (field (name "PART NUMBER") "CRCW0805270RFKEA") (field (name "MANUFACTURER") "Vishay Dale"))
      (libsource (lib "Altium Content Vault") (part "RES"))
    )
    (comp (ref "R35")
      (value "4.7k/0805")
      (footprint "RESC2013X50X30ML20T20")
      (fields (field (name "PART NUMBER") "CRCW0805270RFKEA") (field (name "MANUFACTURER") "Vishay Dale"))
      (libsource (lib "Altium Content Vault") (part "RES"))
    )
    (comp (ref "R36")
      (value "4.7k/0805")
      (footprint "RESC2013X50X30ML20T20")
      (fields (field (name "PART NUMBER") "CRCW0805270RFKEA") (field (name "MANUFACTURER") "Vishay Dale"))
      (libsource (lib "Altium Content Vault") (part "RES"))
    )
    (comp (ref "R37")
      (value "10k/0805")
      (footprint "RESC2013X50X30ML20T20")
      (fields (field (name "PART NUMBER") "CRCW0805270RFKEA") (field (name "MANUFACTURER") "Vishay Dale"))
      (libsource (lib "Altium Content Vault") (part "RES"))
    )
    (comp (ref "R38")
      (value "3.3k/0805")
      (footprint "RESC2013X50X30ML20T20")
      (fields (field (name "PART NUMBER") "CRCW0805270RFKEA") (field (name "MANUFACTURER") "Vishay Dale"))
      (libsource (lib "Altium Content Vault") (part "RES"))
    )
    (comp (ref "R39")
      (value "10k/0805")
      (footprint "RESC2013X50X30ML20T20")
      (fields (field (name "PART NUMBER") "CRCW0805270RFKEA") (field (name "MANUFACTURER") "Vishay Dale"))
      (libsource (lib "Altium Content Vault") (part "RES"))
    )
    (comp (ref "R40")
      (value "10k/0805")
      (footprint "RESC2013X50X30ML20T20")
      (fields (field (name "PART NUMBER") "CRCW0805270RFKEA") (field (name "MANUFACTURER") "Vishay Dale"))
      (libsource (lib "Altium Content Vault") (part "RES"))
    )
    (comp (ref "R41")
      (value "12.4k/0805")
      (footprint "RESC2013X50X30ML20T20")
      (fields (field (name "PART NUMBER") "CRCW0805270RFKEA") (field (name "MANUFACTURER") "Vishay Dale"))
      (libsource (lib "Altium Content Vault") (part "RES"))
    )
    (comp (ref "R42")
      (value "10k/0805")
      (footprint "RESC2013X50X30ML20T20")
      (fields (field (name "PART NUMBER") "CRCW0805270RFKEA") (field (name "MANUFACTURER") "Vishay Dale"))
      (libsource (lib "Altium Content Vault") (part "RES"))
    )
    (comp (ref "R43")
      (value "10k/0805")
      (footprint "RESC2013X50X30ML20T20")
      (fields (field (name "PART NUMBER") "CRCW0805270RFKEA") (field (name "MANUFACTURER") "Vishay Dale"))
      (libsource (lib "Altium Content Vault") (part "RES"))
    )
    (comp (ref "R44")
      (value "1.2k/0805")
      (footprint "RESC2013X50X30ML20T20")
      (fields (field (name "PART NUMBER") "CRCW0805270RFKEA") (field (name "MANUFACTURER") "Vishay Dale"))
      (libsource (lib "Altium Content Vault") (part "RES"))
    )
    (comp (ref "R45")
      (value "953R/0805")
      (footprint "RESC2013X50X30ML20T20")
      (fields (field (name "PART NUMBER") "CRCW0805270RFKEA") (field (name "MANUFACTURER") "Vishay Dale"))
      (libsource (lib "Altium Content Vault") (part "RES"))
    )
    (comp (ref "R46")
      (value "20.5k/0805")
      (footprint "RESC2013X50X30ML20T20")
      (fields (field (name "PART NUMBER") "CRCW0805270RFKEA") (field (name "MANUFACTURER") "Vishay Dale"))
      (libsource (lib "Altium Content Vault") (part "RES"))
    )
    (comp (ref "R47")
      (value "47k/0805.")
      (footprint "RESC2013X50X30ML20T20")
      (fields (field (name "PART NUMBER") "CRCW0805270RFKEA") (field (name "MANUFACTURER") "Vishay Dale"))
      (libsource (lib "Altium Content Vault") (part "RES"))
    )
    (comp (ref "R48")
      (value "10k/0805")
      (footprint "RESC2013X50X30ML20T20")
      (fields (field (name "PART NUMBER") "CRCW0805270RFKEA") (field (name "MANUFACTURER") "Vishay Dale"))
      (libsource (lib "Altium Content Vault") (part "RES"))
    )
    (comp (ref "R49")
      (value "20k/0805")
      (footprint "RESC2013X50X30ML20T20")
      (fields (field (name "PART NUMBER") "CRCW0805270RFKEA") (field (name "MANUFACTURER") "Vishay Dale"))
      (libsource (lib "Altium Content Vault") (part "RES"))
    )
    (comp (ref "R50")
      (value "4.7k/0805")
      (footprint "RESC2013X50X30ML20T20")
      (fields (field (name "PART NUMBER") "CRCW0805270RFKEA") (field (name "MANUFACTURER") "Vishay Dale"))
      (libsource (lib "Altium Content Vault") (part "RES"))
    )
    (comp (ref "R51")
      (value "3296W-1-102ALF")
      (footprint "SamacSys:3296W-1")
      (description "Resistor")
      (fields (field (name "MOUSER PART NUMBER") "652-3296W-1-102ALF"))
      (libsource (lib "*") (part "3296W-1-102ALF"))
    )
    (comp (ref "R52")
      (value "10k/0805")
      (footprint "RESC2013X50X30ML20T20")
      (fields (field (name "PART NUMBER") "CRCW0805270RFKEA") (field (name "MANUFACTURER") "Vishay Dale"))
      (libsource (lib "Altium Content Vault") (part "RES"))
    )
    (comp (ref "R53")
      (value "10k/0805")
      (footprint "RESC2013X50X30ML20T20")
      (fields (field (name "PART NUMBER") "CRCW0805270RFKEA") (field (name "MANUFACTURER") "Vishay Dale"))
      (libsource (lib "Altium Content Vault") (part "RES"))
    )
    (comp (ref "R54")
      (value "3.3k/0805")
      (footprint "RESC2013X50X30ML20T20")
      (fields (field (name "PART NUMBER") "CRCW0805270RFKEA") (field (name "MANUFACTURER") "Vishay Dale"))
      (libsource (lib "Altium Content Vault") (part "RES"))
    )
    (comp (ref "R55")
      (value "10k/0805")
      (footprint "RESC2013X50X30ML20T20")
      (fields (field (name "PART NUMBER") "CRCW0805270RFKEA") (field (name "MANUFACTURER") "Vishay Dale"))
      (libsource (lib "Altium Content Vault") (part "RES"))
    )
    (comp (ref "R56")
      (value "10k/0805")
      (footprint "RESC2013X50X30ML20T20")
      (fields (field (name "PART NUMBER") "CRCW0805270RFKEA") (field (name "MANUFACTURER") "Vishay Dale"))
      (libsource (lib "Altium Content Vault") (part "RES"))
    )
    (comp (ref "R57")
      (value "10k/0805")
      (footprint "RESC2013X50X30ML20T20")
      (fields (field (name "PART NUMBER") "CRCW0805270RFKEA") (field (name "MANUFACTURER") "Vishay Dale"))
      (libsource (lib "Altium Content Vault") (part "RES"))
    )
    (comp (ref "R58")
      (value "10k/0805")
      (footprint "RESC2013X50X30ML20T20")
      (fields (field (name "PART NUMBER") "CRCW0805270RFKEA") (field (name "MANUFACTURER") "Vishay Dale"))
      (libsource (lib "Altium Content Vault") (part "RES"))
    )
    (comp (ref "R59")
      (value "10k/0805")
      (footprint "RESC2013X50X30ML20T20")
      (fields (field (name "PART NUMBER") "CRCW0805270RFKEA") (field (name "MANUFACTURER") "Vishay Dale"))
      (libsource (lib "Altium Content Vault") (part "RES"))
    )
    (comp (ref "R60")
      (value "10k/0805")
      (footprint "RESC2013X50X30ML20T20")
      (fields (field (name "PART NUMBER") "CRCW0805270RFKEA") (field (name "MANUFACTURER") "Vishay Dale"))
      (libsource (lib "Altium Content Vault") (part "RES"))
    )
    (comp (ref "R61")
      (value "1.2k/0805")
      (footprint "RESC2013X50X30ML20T20")
      (fields (field (name "PART NUMBER") "CRCW0805270RFKEA") (field (name "MANUFACTURER") "Vishay Dale"))
      (libsource (lib "Altium Content Vault") (part "RES"))
    )
    (comp (ref "R62")
      (value "953R/0805")
      (footprint "RESC2013X50X30ML20T20")
      (fields (field (name "PART NUMBER") "CRCW0805270RFKEA") (field (name "MANUFACTURER") "Vishay Dale"))
      (libsource (lib "Altium Content Vault") (part "RES"))
    )
    (comp (ref "R63")
      (value "10k/0805")
      (footprint "RESC2013X50X30ML20T20")
      (fields (field (name "PART NUMBER") "CRCW0805270RFKEA") (field (name "MANUFACTURER") "Vishay Dale"))
      (libsource (lib "Altium Content Vault") (part "RES"))
    )
    (comp (ref "R64")
      (value "10k/0805")
      (footprint "RESC2013X50X30ML20T20")
      (fields (field (name "PART NUMBER") "CRCW0805270RFKEA") (field (name "MANUFACTURER") "Vishay Dale"))
      (libsource (lib "Altium Content Vault") (part "RES"))
    )
    (comp (ref "R65")
      (value "10k/0805")
      (footprint "RESC2013X50X30ML20T20")
      (fields (field (name "PART NUMBER") "CRCW0805270RFKEA") (field (name "MANUFACTURER") "Vishay Dale"))
      (libsource (lib "Altium Content Vault") (part "RES"))
    )
    (comp (ref "R66")
      (value "1M/0805")
      (footprint "RESC2013X50X30ML20T20")
      (fields (field (name "PART NUMBER") "CRCW0805270RFKEA") (field (name "MANUFACTURER") "Vishay Dale"))
      (libsource (lib "Altium Content Vault") (part "RES"))
    )
    (comp (ref "R67")
      (value "4.7k/0805")
      (footprint "RESC2013X50X30ML20T20")
      (fields (field (name "PART NUMBER") "CRCW0805270RFKEA") (field (name "MANUFACTURER") "Vishay Dale"))
      (libsource (lib "Altium Content Vault") (part "RES"))
    )
    (comp (ref "R68")
      (value "10k/0805")
      (footprint "RESC2013X50X30ML20T20")
      (fields (field (name "PART NUMBER") "CRCW0805270RFKEA") (field (name "MANUFACTURER") "Vishay Dale"))
      (libsource (lib "Altium Content Vault") (part "RES"))
    )
    (comp (ref "R69")
      (value "20.5k/0805")
      (footprint "RESC2013X50X30ML20T20")
      (fields (field (name "PART NUMBER") "CRCW0805270RFKEA") (field (name "MANUFACTURER") "Vishay Dale"))
      (libsource (lib "Altium Content Vault") (part "RES"))
    )
    (comp (ref "R70")
      (value "47k//0805")
      (footprint "RESC2013X50X30ML20T20")
      (fields (field (name "PART NUMBER") "CRCW0805270RFKEA") (field (name "MANUFACTURER") "Vishay Dale"))
      (libsource (lib "Altium Content Vault") (part "RES"))
    )
    (comp (ref "R71")
      (value "10k/0805")
      (footprint "RESC2013X50X30ML20T20")
      (fields (field (name "PART NUMBER") "CRCW0805270RFKEA") (field (name "MANUFACTURER") "Vishay Dale"))
      (libsource (lib "Altium Content Vault") (part "RES"))
    )
    (comp (ref "R72")
      (value "4.7k/0805")
      (footprint "RESC2013X50X30ML20T20")
      (fields (field (name "PART NUMBER") "CRCW0805270RFKEA") (field (name "MANUFACTURER") "Vishay Dale"))
      (libsource (lib "Altium Content Vault") (part "RES"))
    )
    (comp (ref "R73")
      (value "10k/0805")
      (footprint "RESC2013X50X30ML20T20")
      (fields (field (name "PART NUMBER") "CRCW0805270RFKEA") (field (name "MANUFACTURER") "Vishay Dale"))
      (libsource (lib "Altium Content Vault") (part "RES"))
    )
    (comp (ref "R74")
      (value "10/0805")
      (footprint "RESC2013X50X30ML20T20")
      (fields (field (name "PART NUMBER") "CRCW0805270RFKEA") (field (name "MANUFACTURER") "Vishay Dale"))
      (libsource (lib "Altium Content Vault") (part "RES"))
    )
    (comp (ref "R75")
      (value "49.9/0805")
      (footprint "RESC2013X50X30ML20T20")
      (fields (field (name "PART NUMBER") "CRCW0805270RFKEA") (field (name "MANUFACTURER") "Vishay Dale"))
      (libsource (lib "Altium Content Vault") (part "RES"))
    )
    (comp (ref "R76")
      (value "49.9/0805")
      (footprint "RESC2013X50X30ML20T20")
      (fields (field (name "PART NUMBER") "CRCW0805270RFKEA") (field (name "MANUFACTURER") "Vishay Dale"))
      (libsource (lib "Altium Content Vault") (part "RES"))
    )
    (comp (ref "R77")
      (value "33/0805")
      (footprint "RESC2013X50X30ML20T20")
      (fields (field (name "PART NUMBER") "CRCW0805270RFKEA") (field (name "MANUFACTURER") "Vishay Dale"))
      (libsource (lib "Altium Content Vault") (part "RES"))
    )
    (comp (ref "R78")
      (value "3296W-1-102ALF")
      (footprint "SamacSys:3296W-1")
      (description "Resistor")
      (fields (field (name "MOUSER PART NUMBER") "652-3296W-1-102ALF"))
      (libsource (lib "*") (part "3296W-1-102ALF"))
    )
    (comp (ref "R79")
      (value "33/0805")
      (footprint "RESC2013X50X30ML20T20")
      (fields (field (name "PART NUMBER") "CRCW0805270RFKEA") (field (name "MANUFACTURER") "Vishay Dale"))
      (libsource (lib "Altium Content Vault") (part "RES"))
    )
    (comp (ref "R80")
      (value "330/0805")
      (footprint "RESC2013X50X30ML20T20")
      (fields (field (name "PART NUMBER") "CRCW0805270RFKEA") (field (name "MANUFACTURER") "Vishay Dale"))
      (libsource (lib "Altium Content Vault") (part "RES"))
    )
    (comp (ref "R81")
      (value "33/0805")
      (footprint "RESC2013X50X30ML20T20")
      (fields (field (name "PART NUMBER") "CRCW0805270RFKEA") (field (name "MANUFACTURER") "Vishay Dale"))
      (libsource (lib "Altium Content Vault") (part "RES"))
    )
    (comp (ref "R82")
      (value "330/0805")
      (footprint "RESC2013X50X30ML20T20")
      (fields (field (name "PART NUMBER") "CRCW0805270RFKEA") (field (name "MANUFACTURER") "Vishay Dale"))
      (libsource (lib "Altium Content Vault") (part "RES"))
    )
    (comp (ref "R83")
      (value "33/0805")
      (footprint "RESC2013X50X30ML20T20")
      (fields (field (name "PART NUMBER") "CRCW0805270RFKEA") (field (name "MANUFACTURER") "Vishay Dale"))
      (libsource (lib "Altium Content Vault") (part "RES"))
    )
    (comp (ref "R84")
      (value "4.7k/0805")
      (footprint "RESC2013X50X30ML20T20")
      (fields (field (name "PART NUMBER") "CRCW0805270RFKEA") (field (name "MANUFACTURER") "Vishay Dale"))
      (libsource (lib "Altium Content Vault") (part "RES"))
    )
    (comp (ref "R85")
      (value "10k/0805")
      (footprint "RESC2013X50X30ML20T20")
      (fields (field (name "PART NUMBER") "CRCW0805270RFKEA") (field (name "MANUFACTURER") "Vishay Dale"))
      (libsource (lib "Altium Content Vault") (part "RES"))
    )
    (comp (ref "R86")
      (value "49.9/0805")
      (footprint "RESC2013X50X30ML20T20")
      (fields (field (name "PART NUMBER") "CRCW0805270RFKEA") (field (name "MANUFACTURER") "Vishay Dale"))
      (libsource (lib "Altium Content Vault") (part "RES"))
    )
    (comp (ref "R87")
      (value "49.9/0805")
      (footprint "RESC2013X50X30ML20T20")
      (fields (field (name "PART NUMBER") "CRCW0805270RFKEA") (field (name "MANUFACTURER") "Vishay Dale"))
      (libsource (lib "Altium Content Vault") (part "RES"))
    )
    (comp (ref "R88")
      (value "1k/0805")
      (footprint "RESC2013X50X30ML20T20")
      (fields (field (name "PART NUMBER") "CRCW0805270RFKEA") (field (name "MANUFACTURER") "Vishay Dale"))
      (libsource (lib "Altium Content Vault") (part "RES"))
    )
    (comp (ref "R89")
      (value "1k/0805")
      (footprint "RESC2013X50X30ML20T20")
      (fields (field (name "PART NUMBER") "CRCW0805270RFKEA") (field (name "MANUFACTURER") "Vishay Dale"))
      (libsource (lib "Altium Content Vault") (part "RES"))
    )
    (comp (ref "R90")
      (value "1k/0805")
      (footprint "RESC2013X50X30ML20T20")
      (fields (field (name "PART NUMBER") "CRCW0805270RFKEA") (field (name "MANUFACTURER") "Vishay Dale"))
      (libsource (lib "Altium Content Vault") (part "RES"))
    )
    (comp (ref "R91")
      (value "1k/0805")
      (footprint "RESC2013X50X30ML20T20")
      (fields (field (name "PART NUMBER") "CRCW0805270RFKEA") (field (name "MANUFACTURER") "Vishay Dale"))
      (libsource (lib "Altium Content Vault") (part "RES"))
    )
    (comp (ref "R92")
      (value "4.7k/0805")
      (footprint "RESC2013X50X30ML20T20")
      (fields (field (name "PART NUMBER") "CRCW0805270RFKEA") (field (name "MANUFACTURER") "Vishay Dale"))
      (libsource (lib "Altium Content Vault") (part "RES"))
    )
    (comp (ref "R93")
      (value "4.7k/0805")
      (footprint "RESC2013X50X30ML20T20")
      (fields (field (name "PART NUMBER") "CRCW0805270RFKEA") (field (name "MANUFACTURER") "Vishay Dale"))
      (libsource (lib "Altium Content Vault") (part "RES"))
    )
    (comp (ref "R94")
      (value "4.7k/0805")
      (footprint "RESC2013X50X30ML20T20")
      (fields (field (name "PART NUMBER") "CRCW0805270RFKEA") (field (name "MANUFACTURER") "Vishay Dale"))
      (libsource (lib "Altium Content Vault") (part "RES"))
    )
    (comp (ref "R95")
      (value "4.7k/0805")
      (footprint "RESC2013X50X30ML20T20")
      (fields (field (name "PART NUMBER") "CRCW0805270RFKEA") (field (name "MANUFACTURER") "Vishay Dale"))
      (libsource (lib "Altium Content Vault") (part "RES"))
    )
    (comp (ref "U1")
      (value "LM2576-5.0WU")
      (footprint "SamacSys:MICROCHIP_TO-263")
      (description "Undefined or Miscellaneous")
      (fields (field (name "MOUSER PART NUMBER") "998-LM2576-5.0WU"))
      (libsource (lib "*") (part "LM2576-5.0WU"))
    )
    (comp (ref "U2")
      (value "ST485BDR")
      (footprint "FP-SO-8-0016023-IPC_C")
      (description "IC TXRX 5V RS485/422 LP 8-SOIC")
      (fields
        (field (name "OCTOPART") "https://octopart.com/st485bdr-stmicroelectronics-503862")
        (field (name "MANUFACTURER") "STMicroelectronics")
      )
      (libsource (lib "Altium Content Vault") (part "b55209371e3dc3bf5284ff8ac5b7fc6"))
    )
    (comp (ref "U3")
      (value "LM1117GS-3.3-HTC")
      (footprint "DCY0004A_L")
      (description "800mA Low-Dropout Linear Regulator, 4-pin SOT-223, Pb-Free")
      (fields
        (field (name "PARTNUMBER") "LM1117MP-3.3/NOPB")
        (field (name "MANUFACTURER") "Texas Instruments")
      )
      (libsource (lib "Altium Content Vault") (part "PM-REG-LM1086-SOT4"))
    )
    (comp (ref "U4")
      (value "STM32F072C8T6")
      (footprint "STM-LQFP48_N")
      (fields (field (name "MANUFACTURER") "STMicroelectronics"))
      (libsource (lib "Altium Content Vault") (part "MC-ARM-STM32F07X-LQFP48"))
    )
    (comp (ref "U5")
      (value "LM358DR")
      (footprint "FP-D0008A-MFG")
      (description "IC OPAMP GP 2 CIRCUIT 8SOIC")
      (libsource (lib "Altium Content Vault") (part "0afdfe5f461d2cdd85604ff8654be97"))
    )
    (comp (ref "Y1")
      (value "8Mhz")
      (footprint "FOX-FOXSLF080-20")
      (description "Resistance Weld Thru-Hole Crystal, 8 MHz, -20 to 70 degC, 2-Pin THD, RoHS, Bulk")
      (libsource (lib "Altium Content Vault") (part "XTAL-1-2-2"))
    )
    (comp (ref "Y2")
      (value "25mhz")
      (footprint "FOX-FOXSLF080-20")
      (description "Resistance Weld Thru-Hole Crystal, 8 MHz, -20 to 70 degC, 2-Pin THD, RoHS, Bulk")
      (libsource (lib "Altium Content Vault") (part "XTAL-1-2-2"))
    )
  )
  (nets
    (net (code "1") (name "+3.3") (class "Default")
      (node (ref "C12") (pin "1") (pinfunction "1_1") (pintype "passive"))
      (node (ref "C13") (pin "1") (pinfunction "1_1") (pintype "passive"))
      (node (ref "C14") (pin "1") (pinfunction "1_1") (pintype "passive"))
      (node (ref "C15") (pin "1") (pinfunction "1_1") (pintype "passive"))
      (node (ref "C16") (pin "1") (pinfunction "1_1") (pintype "passive"))
      (node (ref "C17") (pin "1") (pinfunction "1_1") (pintype "passive"))
      (node (ref "C2") (pin "1") (pinfunction "1_1") (pintype "passive"))
      (node (ref "C3") (pin "1") (pinfunction "1_1") (pintype "passive"))
      (node (ref "C30") (pin "1") (pinfunction "1_1") (pintype "passive"))
      (node (ref "C31") (pin "1") (pinfunction "1_1") (pintype "passive"))
      (node (ref "C34") (pin "1") (pinfunction "1_1") (pintype "passive"))
      (node (ref "C38") (pin "1") (pinfunction "1_1") (pintype "passive"))
      (node (ref "C7") (pin "1") (pinfunction "1_1") (pintype "passive"))
      (node (ref "D2") (pin "1") (pinfunction "K_1") (pintype "passive"))
      (node (ref "D4") (pin "1") (pinfunction "K_1") (pintype "passive"))
      (node (ref "D6") (pin "1") (pinfunction "K_1") (pintype "passive"))
      (node (ref "D9") (pin "1") (pinfunction "K_1") (pintype "passive"))
      (node (ref "IC1") (pin "28") (pinfunction "VDD_28") (pintype "passive"))
      (node (ref "J17") (pin "12") (pinfunction "12_12") (pintype "passive"))
      (node (ref "J17") (pin "9") (pinfunction "9_9") (pintype "passive"))
      (node (ref "J3") (pin "1") (pinfunction "1_1") (pintype "passive"))
      (node (ref "L2") (pin "1") (pinfunction "1_1") (pintype "passive"))
      (node (ref "R1") (pin "2") (pinfunction "2_2") (pintype "passive"))
      (node (ref "R12") (pin "2") (pinfunction "2_2") (pintype "passive"))
      (node (ref "R2") (pin "2") (pinfunction "2_2") (pintype "passive"))
      (node (ref "R20") (pin "2") (pinfunction "2_2") (pintype "passive"))
      (node (ref "R28") (pin "2") (pinfunction "2_2") (pintype "passive"))
      (node (ref "R3") (pin "2") (pinfunction "2_2") (pintype "passive"))
      (node (ref "R36") (pin "2") (pinfunction "2_2") (pintype "passive"))
      (node (ref "R4") (pin "2") (pinfunction "2_2") (pintype "passive"))
      (node (ref "R42") (pin "2") (pinfunction "2_2") (pintype "passive"))
      (node (ref "R43") (pin "2") (pinfunction "2_2") (pintype "passive"))
      (node (ref "R55") (pin "1") (pinfunction "1_1") (pintype "passive"))
      (node (ref "R6") (pin "2") (pinfunction "2_2") (pintype "passive"))
      (node (ref "R63") (pin "1") (pinfunction "1_1") (pintype "passive"))
      (node (ref "R64") (pin "1") (pinfunction "1_1") (pintype "passive"))
      (node (ref "R65") (pin "1") (pinfunction "1_1") (pintype "passive"))
      (node (ref "R88") (pin "1") (pinfunction "1_1") (pintype "passive"))
      (node (ref "R89") (pin "1") (pinfunction "1_1") (pintype "passive"))
      (node (ref "R90") (pin "1") (pinfunction "1_1") (pintype "passive"))
      (node (ref "R91") (pin "1") (pinfunction "1_1") (pintype "passive"))
      (node (ref "U2") (pin "8") (pinfunction "VCC_8") (pintype "power_in"))
      (node (ref "U3") (pin "2") (pinfunction "OUT_2") (pintype "power_in"))
      (node (ref "U3") (pin "4") (pinfunction "TAB_4") (pintype "power_in"))
      (node (ref "U4") (pin "1") (pinfunction "VBAT_1") (pintype "power_in"))
      (node (ref "U4") (pin "24") (pinfunction "VDD_24") (pintype "power_in"))
      (node (ref "U4") (pin "36") (pinfunction "VDDIO2_36") (pintype "power_in"))
      (node (ref "U4") (pin "48") (pinfunction "VDD_48") (pintype "power_in"))
      (node (ref "U4") (pin "9") (pinfunction "VDDA_9") (pintype "power_in"))
    )
    (net (code "2") (name "+5") (class "Default")
      (node (ref "C1") (pin "1") (pinfunction "+_1") (pintype "passive"))
      (node (ref "C6") (pin "1") (pinfunction "1_1") (pintype "passive"))
      (node (ref "L1") (pin "2") (pinfunction "2_2") (pintype "passive"))
      (node (ref "U1") (pin "4") (pinfunction "FEEDBACK_4") (pintype "passive"))
      (node (ref "U3") (pin "3") (pinfunction "IN_3") (pintype "power_in"))
    )
    (net (code "3") (name "+24") (class "Default")
      (node (ref "C28") (pin "1") (pinfunction "1_1") (pintype "passive"))
      (node (ref "C4") (pin "1") (pinfunction "+_1") (pintype "passive"))
      (node (ref "D11") (pin "1") (pinfunction "K_1") (pintype "passive"))
      (node (ref "D12") (pin "1") (pinfunction "K_1") (pintype "passive"))
      (node (ref "D13") (pin "1") (pinfunction "K_1") (pintype "passive"))
      (node (ref "D8") (pin "1") (pinfunction "K_1") (pintype "passive"))
      (node (ref "J1") (pin "1") (pinfunction "1_1") (pintype "passive"))
      (node (ref "K1") (pin "4") (pinfunction "COIL_2_4") (pintype "passive"))
      (node (ref "K2") (pin "4") (pinfunction "COIL_2_4") (pintype "passive"))
      (node (ref "K3") (pin "4") (pinfunction "COIL_2_4") (pintype "passive"))
      (node (ref "K4") (pin "4") (pinfunction "COIL_2_4") (pintype "passive"))
      (node (ref "R11") (pin "2") (pinfunction "2_2") (pintype "passive"))
      (node (ref "R21") (pin "2") (pinfunction "2_2") (pintype "passive"))
      (node (ref "R27") (pin "2") (pinfunction "2_2") (pintype "passive"))
      (node (ref "R35") (pin "2") (pinfunction "2_2") (pintype "passive"))
      (node (ref "R92") (pin "1") (pinfunction "1_1") (pintype "passive"))
      (node (ref "R93") (pin "1") (pinfunction "1_1") (pintype "passive"))
      (node (ref "R94") (pin "1") (pinfunction "1_1") (pintype "passive"))
      (node (ref "R95") (pin "1") (pinfunction "1_1") (pintype "passive"))
      (node (ref "U1") (pin "1") (pinfunction "VIN_1") (pintype "passive"))
      (node (ref "U5") (pin "8") (pinfunction "V+_8") (pintype "power_in"))
    )
    (net (code "4") (name "+A3.3") (class "Default")
      (node (ref "C21") (pin "1") (pinfunction "1_1") (pintype "passive"))
      (node (ref "C22") (pin "1") (pinfunction "1_1") (pintype "passive"))
      (node (ref "C23") (pin "1") (pinfunction "1_1") (pintype "passive"))
      (node (ref "C24") (pin "1") (pinfunction "1_1") (pintype "passive"))
      (node (ref "C25") (pin "1") (pinfunction "1_1") (pintype "passive"))
      (node (ref "C26") (pin "1") (pinfunction "1_1") (pintype "passive"))
      (node (ref "C27") (pin "1") (pinfunction "1_1") (pintype "passive"))
      (node (ref "C37") (pin "1") (pinfunction "1_1") (pintype "passive"))
      (node (ref "C39") (pin "1") (pinfunction "1_1") (pintype "passive"))
      (node (ref "IC1") (pin "11") (pinfunction "AVDD_3_11") (pintype "passive"))
      (node (ref "IC1") (pin "15") (pinfunction "AVDD_4_15") (pintype "passive"))
      (node (ref "IC1") (pin "17") (pinfunction "AVDD_5_17") (pintype "passive"))
      (node (ref "IC1") (pin "21") (pinfunction "AVDD_6_21") (pintype "passive"))
      (node (ref "IC1") (pin "4") (pinfunction "AVDD_1_4") (pintype "passive"))
      (node (ref "IC1") (pin "8") (pinfunction "AVDD_2_8") (pintype "passive"))
      (node (ref "L2") (pin "2") (pinfunction "2_2") (pintype "passive"))
      (node (ref "R74") (pin "2") (pinfunction "2_2") (pintype "passive"))
      (node (ref "R75") (pin "2") (pinfunction "2_2") (pintype "passive"))
      (node (ref "R76") (pin "2") (pinfunction "2_2") (pintype "passive"))
    )
    (net (code "5") (name "/ACTLED") (class "Default")
      (node (ref "IC1") (pin "27") (pinfunction "ACTLED_27") (pintype "passive"))
      (node (ref "R80") (pin "2") (pinfunction "2_2") (pintype "passive"))
    )
    (net (code "6") (name "/ANOLOG_IN_1") (class "Default")
      (node (ref "C10") (pin "1") (pinfunction "1_1") (pintype "passive"))
      (node (ref "D2") (pin "2") (pinfunction "A_2") (pintype "passive"))
      (node (ref "D3") (pin "1") (pinfunction "K_1") (pintype "passive"))
      (node (ref "R13") (pin "2") (pinfunction "2_2") (pintype "passive"))
      (node (ref "R14") (pin "2") (pinfunction "2_2") (pintype "passive"))
      (node (ref "R17") (pin "2") (pinfunction "2_2") (pintype "passive"))
      (node (ref "U4") (pin "10") (pinfunction "PA0_10") (pintype "bidirectional"))
    )
    (net (code "7") (name "/ANOLOG_IN_2") (class "Default")
      (node (ref "C18") (pin "1") (pinfunction "1_1") (pintype "passive"))
      (node (ref "D4") (pin "2") (pinfunction "A_2") (pintype "passive"))
      (node (ref "D5") (pin "1") (pinfunction "K_1") (pintype "passive"))
      (node (ref "R23") (pin "2") (pinfunction "2_2") (pintype "passive"))
      (node (ref "R25") (pin "2") (pinfunction "2_2") (pintype "passive"))
      (node (ref "R26") (pin "2") (pinfunction "2_2") (pintype "passive"))
      (node (ref "U4") (pin "11") (pinfunction "PA1_11") (pintype "bidirectional"))
    )
    (net (code "8") (name "/ANOLOG_IN_3") (class "Default")
      (node (ref "C29") (pin "1") (pinfunction "1_1") (pintype "passive"))
      (node (ref "D6") (pin "2") (pinfunction "A_2") (pintype "passive"))
      (node (ref "D7") (pin "1") (pinfunction "K_1") (pintype "passive"))
      (node (ref "R34") (pin "2") (pinfunction "2_2") (pintype "passive"))
      (node (ref "R37") (pin "2") (pinfunction "2_2") (pintype "passive"))
      (node (ref "R38") (pin "2") (pinfunction "2_2") (pintype "passive"))
      (node (ref "U4") (pin "12") (pinfunction "PA2_12") (pintype "bidirectional"))
    )
    (net (code "9") (name "/ANOLOG_IN_4") (class "Default")
      (node (ref "C33") (pin "1") (pinfunction "1_1") (pintype "passive"))
      (node (ref "D10") (pin "1") (pinfunction "K_1") (pintype "passive"))
      (node (ref "D9") (pin "2") (pinfunction "A_2") (pintype "passive"))
      (node (ref "R49") (pin "2") (pinfunction "2_2") (pintype "passive"))
      (node (ref "R52") (pin "2") (pinfunction "2_2") (pintype "passive"))
      (node (ref "R54") (pin "2") (pinfunction "2_2") (pintype "passive"))
      (node (ref "U4") (pin "13") (pinfunction "PA3_13") (pintype "bidirectional"))
    )
    (net (code "10") (name "/ANOLOG_OUT_1") (class "Default")
      (node (ref "C32") (pin "1") (pinfunction "1_1") (pintype "passive"))
      (node (ref "R47") (pin "2") (pinfunction "2_2") (pintype "passive"))
      (node (ref "U4") (pin "14") (pinfunction "PA4_14") (pintype "bidirectional"))
      (node (ref "U5") (pin "3") (pinfunction "IN1+_3") (pintype "tri_state"))
    )
    (net (code "11") (name "/ANOLOG_OUT_2") (class "Default")
      (node (ref "C40") (pin "1") (pinfunction "1_1") (pintype "passive"))
      (node (ref "R70") (pin "2") (pinfunction "2_2") (pintype "passive"))
      (node (ref "U4") (pin "15") (pinfunction "PA5_15") (pintype "bidirectional"))
      (node (ref "U5") (pin "5") (pinfunction "IN2+_5") (pintype "tri_state"))
    )
    (net (code "12") (name "/CRYSTAL_IN") (class "Default")
      (node (ref "C36") (pin "2") (pinfunction "2_2") (pintype "passive"))
      (node (ref "IC1") (pin "30") (pinfunction "XI/CLKIN_30") (pintype "passive"))
      (node (ref "R66") (pin "1") (pinfunction "1_1") (pintype "passive"))
      (node (ref "Y2") (pin "2") (pinfunction "2_2") (pintype "passive"))
    )
    (net (code "13") (name "/CRYSTAL_OUT") (class "Default")
      (node (ref "C35") (pin "2") (pinfunction "2_2") (pintype "passive"))
      (node (ref "IC1") (pin "31") (pinfunction "XO_31") (pintype "passive"))
      (node (ref "R66") (pin "2") (pinfunction "2_2") (pintype "passive"))
      (node (ref "Y2") (pin "1") (pinfunction "1_1") (pintype "passive"))
    )
    (net (code "14") (name "/D_out_1") (class "Default")
      (node (ref "R50") (pin "1") (pinfunction "1_1") (pintype "passive"))
      (node (ref "U4") (pin "46") (pinfunction "PB9_46") (pintype "bidirectional"))
    )
    (net (code "15") (name "/D_out_2") (class "Default")
      (node (ref "R67") (pin "1") (pinfunction "1_1") (pintype "passive"))
      (node (ref "U4") (pin "2") (pinfunction "PC13_2") (pintype "bidirectional"))
    )
    (net (code "16") (name "/D_out_3") (class "Default")
      (node (ref "R72") (pin "1") (pinfunction "1_1") (pintype "passive"))
      (node (ref "U4") (pin "3") (pinfunction "PC14-OSC32_IN(PC14)_3") (pintype "bidirectional"))
    )
    (net (code "17") (name "/D_out_4") (class "Default")
      (node (ref "R84") (pin "1") (pinfunction "1_1") (pintype "passive"))
      (node (ref "U4") (pin "4") (pinfunction "PC15-OSC32_OUT(PC15)_4") (pintype "bidirectional"))
    )
    (net (code "18") (name "/LINKLED") (class "Default")
      (node (ref "IC1") (pin "25") (pinfunction "LINKLED_25") (pintype "passive"))
      (node (ref "R82") (pin "2") (pinfunction "2_2") (pintype "passive"))
    )
    (net (code "19") (name "/NRST") (class "Default")
      (node (ref "C8") (pin "1") (pinfunction "1_1") (pintype "passive"))
      (node (ref "J3") (pin "5") (pinfunction "5_5") (pintype "passive"))
      (node (ref "R6") (pin "1") (pinfunction "1_1") (pintype "passive"))
      (node (ref "U4") (pin "7") (pinfunction "NRST_7") (pintype "bidirectional"))
    )
    (net (code "20") (name "/OSC_IN") (class "Default")
      (node (ref "C9") (pin "2") (pinfunction "2_2") (pintype "passive"))
      (node (ref "U4") (pin "5") (pinfunction "PF0-OSC_IN(PF0)_5") (pintype "bidirectional"))
      (node (ref "Y1") (pin "1") (pinfunction "1_1") (pintype "passive"))
    )
    (net (code "21") (name "/OSC_OUT") (class "Default")
      (node (ref "C11") (pin "2") (pinfunction "2_2") (pintype "passive"))
      (node (ref "U4") (pin "6") (pinfunction "PF1-OSC_OUT(PF1)_6") (pintype "bidirectional"))
      (node (ref "Y1") (pin "2") (pinfunction "2_2") (pintype "passive"))
    )
    (net (code "22") (name "/RXN") (class "Default")
      (node (ref "IC1") (pin "5") (pinfunction "RXN_5") (pintype "passive"))
      (node (ref "R83") (pin "1") (pinfunction "1_1") (pintype "passive"))
    )
    (net (code "23") (name "/RXP") (class "Default")
      (node (ref "IC1") (pin "6") (pinfunction "RXP_6") (pintype "passive"))
      (node (ref "R81") (pin "1") (pinfunction "1_1") (pintype "passive"))
    )
    (net (code "24") (name "/SPI_INIT") (class "Default")
      (node (ref "IC1") (pin "36") (pinfunction "INTN_36") (pintype "passive"))
      (node (ref "R43") (pin "1") (pinfunction "1_1") (pintype "passive"))
      (node (ref "U4") (pin "25") (pinfunction "PB12_25") (pintype "bidirectional"))
    )
    (net (code "25") (name "/SPI_MISO") (class "Default")
      (node (ref "IC1") (pin "34") (pinfunction "MISO_34") (pintype "passive"))
      (node (ref "U4") (pin "27") (pinfunction "PB14_27") (pintype "bidirectional"))
    )
    (net (code "26") (name "/SPI_MOSI") (class "Default")
      (node (ref "IC1") (pin "35") (pinfunction "MOSI_35") (pintype "passive"))
      (node (ref "U4") (pin "28") (pinfunction "PB15_28") (pintype "bidirectional"))
    )
    (net (code "27") (name "/SPI_RESET") (class "Default")
      (node (ref "IC1") (pin "37") (pinfunction "RSTN_37") (pintype "passive"))
      (node (ref "R55") (pin "2") (pinfunction "2_2") (pintype "passive"))
      (node (ref "U4") (pin "22") (pinfunction "PB11_22") (pintype "bidirectional"))
    )
    (net (code "28") (name "/SPI_SCK") (class "Default")
      (node (ref "IC1") (pin "33") (pinfunction "SCLK_33") (pintype "passive"))
      (node (ref "U4") (pin "26") (pinfunction "PB13_26") (pintype "bidirectional"))
    )
    (net (code "29") (name "/SPI_SCSN") (class "Default")
      (node (ref "IC1") (pin "32") (pinfunction "SCSN_32") (pintype "passive"))
      (node (ref "R42") (pin "1") (pinfunction "1_1") (pintype "passive"))
      (node (ref "U4") (pin "29") (pinfunction "PA8_29") (pintype "bidirectional"))
    )
    (net (code "30") (name "/SWCLK") (class "Default")
      (node (ref "J3") (pin "2") (pinfunction "2_2") (pintype "passive"))
      (node (ref "U4") (pin "37") (pinfunction "PA14_37") (pintype "bidirectional"))
    )
    (net (code "31") (name "/SWDIO") (class "Default")
      (node (ref "J3") (pin "4") (pinfunction "4_4") (pintype "passive"))
      (node (ref "U4") (pin "34") (pinfunction "PA13_34") (pintype "bidirectional"))
    )
    (net (code "32") (name "/TXN") (class "Default")
      (node (ref "IC1") (pin "1") (pinfunction "TXN_1") (pintype "passive"))
      (node (ref "R79") (pin "1") (pinfunction "1_1") (pintype "passive"))
    )
    (net (code "33") (name "/TXP") (class "Default")
      (node (ref "IC1") (pin "2") (pinfunction "TXP_2") (pintype "passive"))
      (node (ref "R77") (pin "1") (pinfunction "1_1") (pintype "passive"))
    )
    (net (code "34") (name "/USRT1_DE") (class "Default")
      (node (ref "U2") (pin "2") (pinfunction "~{RE}_2") (pintype "input"))
      (node (ref "U2") (pin "3") (pinfunction "DE_3") (pintype "input"))
      (node (ref "U4") (pin "33") (pinfunction "PA12_33") (pintype "bidirectional"))
    )
    (net (code "35") (name "/USRT1_RX") (class "Default")
      (node (ref "LED3") (pin "1") (pinfunction "K_1") (pintype "passive"))
      (node (ref "R7") (pin "1") (pinfunction "1_1") (pintype "passive"))
      (node (ref "U4") (pin "31") (pinfunction "PA10_31") (pintype "bidirectional"))
    )
    (net (code "36") (name "/USRT1_TX") (class "Default")
      (node (ref "LED2") (pin "1") (pinfunction "K_1") (pintype "passive"))
      (node (ref "U2") (pin "4") (pinfunction "DI_4") (pintype "input"))
      (node (ref "U4") (pin "30") (pinfunction "PA9_30") (pintype "bidirectional"))
    )
    (net (code "37") (name "/digital_in_1") (class "Default")
      (node (ref "LED4") (pin "1") (pinfunction "K_1") (pintype "passive"))
      (node (ref "O1") (pin "4") (pinfunction "C_4") (pintype "passive"))
      (node (ref "R12") (pin "1") (pinfunction "1_1") (pintype "passive"))
      (node (ref "U4") (pin "41") (pinfunction "PB5_41") (pintype "bidirectional"))
    )
    (net (code "38") (name "/digital_in_2") (class "Default")
      (node (ref "LED5") (pin "1") (pinfunction "K_1") (pintype "passive"))
      (node (ref "O2") (pin "4") (pinfunction "C_4") (pintype "passive"))
      (node (ref "R20") (pin "1") (pinfunction "1_1") (pintype "passive"))
      (node (ref "U4") (pin "42") (pinfunction "PB6_42") (pintype "bidirectional"))
    )
    (net (code "39") (name "/digital_in_3") (class "Default")
      (node (ref "LED6") (pin "1") (pinfunction "K_1") (pintype "passive"))
      (node (ref "O3") (pin "4") (pinfunction "C_4") (pintype "passive"))
      (node (ref "R28") (pin "1") (pinfunction "1_1") (pintype "passive"))
      (node (ref "U4") (pin "43") (pinfunction "PB7_43") (pintype "bidirectional"))
    )
    (net (code "40") (name "/digital_in_4") (class "Default")
      (node (ref "LED7") (pin "1") (pinfunction "K_1") (pintype "passive"))
      (node (ref "O4") (pin "4") (pinfunction "C_4") (pintype "passive"))
      (node (ref "R36") (pin "1") (pinfunction "1_1") (pintype "passive"))
      (node (ref "U4") (pin "45") (pinfunction "PB8_45") (pintype "bidirectional"))
    )
    (net (code "41") (name "GND") (class "Default")
      (node (ref "C1") (pin "2") (pinfunction "-_2") (pintype "passive"))
      (node (ref "C10") (pin "2") (pinfunction "2_2") (pintype "passive"))
      (node (ref "C11") (pin "1") (pinfunction "1_1") (pintype "passive"))
      (node (ref "C12") (pin "2") (pinfunction "2_2") (pintype "passive"))
      (node (ref "C13") (pin "2") (pinfunction "2_2") (pintype "passive"))
      (node (ref "C14") (pin "2") (pinfunction "2_2") (pintype "passive"))
      (node (ref "C15") (pin "2") (pinfunction "2_2") (pintype "passive"))
      (node (ref "C16") (pin "2") (pinfunction "2_2") (pintype "passive"))
      (node (ref "C17") (pin "2") (pinfunction "2_2") (pintype "passive"))
      (node (ref "C18") (pin "2") (pinfunction "2_2") (pintype "passive"))
      (node (ref "C19") (pin "1") (pinfunction "1_1") (pintype "passive"))
      (node (ref "C2") (pin "2") (pinfunction "2_2") (pintype "passive"))
      (node (ref "C20") (pin "1") (pinfunction "1_1") (pintype "passive"))
      (node (ref "C21") (pin "2") (pinfunction "2_2") (pintype "passive"))
      (node (ref "C22") (pin "2") (pinfunction "2_2") (pintype "passive"))
      (node (ref "C23") (pin "2") (pinfunction "2_2") (pintype "passive"))
      (node (ref "C24") (pin "2") (pinfunction "2_2") (pintype "passive"))
      (node (ref "C25") (pin "2") (pinfunction "2_2") (pintype "passive"))
      (node (ref "C26") (pin "2") (pinfunction "2_2") (pintype "passive"))
      (node (ref "C27") (pin "2") (pinfunction "2_2") (pintype "passive"))
      (node (ref "C28") (pin "2") (pinfunction "2_2") (pintype "passive"))
      (node (ref "C29") (pin "2") (pinfunction "2_2") (pintype "passive"))
      (node (ref "C30") (pin "2") (pinfunction "2_2") (pintype "passive"))
      (node (ref "C31") (pin "2") (pinfunction "2_2") (pintype "passive"))
      (node (ref "C32") (pin "2") (pinfunction "2_2") (pintype "passive"))
      (node (ref "C33") (pin "2") (pinfunction "2_2") (pintype "passive"))
      (node (ref "C34") (pin "2") (pinfunction "2_2") (pintype "passive"))
      (node (ref "C35") (pin "1") (pinfunction "1_1") (pintype "passive"))
      (node (ref "C36") (pin "1") (pinfunction "1_1") (pintype "passive"))
      (node (ref "C37") (pin "2") (pinfunction "2_2") (pintype "passive"))
      (node (ref "C38") (pin "2") (pinfunction "2_2") (pintype "passive"))
      (node (ref "C39") (pin "2") (pinfunction "2_2") (pintype "passive"))
      (node (ref "C4") (pin "2") (pinfunction "-_2") (pintype "passive"))
      (node (ref "C40") (pin "2") (pinfunction "2_2") (pintype "passive"))
      (node (ref "C41") (pin "2") (pinfunction "2_2") (pintype "passive"))
      (node (ref "C44") (pin "2") (pinfunction "2_2") (pintype "passive"))
      (node (ref "C5") (pin "2") (pinfunction "2_2") (pintype "passive"))
      (node (ref "C6") (pin "2") (pinfunction "2_2") (pintype "passive"))
      (node (ref "C7") (pin "2") (pinfunction "2_2") (pintype "passive"))
      (node (ref "C8") (pin "2") (pinfunction "2_2") (pintype "passive"))
      (node (ref "C9") (pin "1") (pinfunction "1_1") (pintype "passive"))
      (node (ref "D1") (pin "2") (pinfunction "A_2") (pintype "passive"))
      (node (ref "D10") (pin "2") (pinfunction "A_2") (pintype "passive"))
      (node (ref "D3") (pin "2") (pinfunction "A_2") (pintype "passive"))
      (node (ref "D5") (pin "2") (pinfunction "A_2") (pintype "passive"))
      (node (ref "D7") (pin "2") (pinfunction "A_2") (pintype "passive"))
      (node (ref "IC1") (pin "14") (pinfunction "AGND_3_14") (pintype "passive"))
      (node (ref "IC1") (pin "16") (pinfunction "AGND_4_16") (pintype "passive"))
      (node (ref "IC1") (pin "19") (pinfunction "AGND_5_19") (pintype "passive"))
      (node (ref "IC1") (pin "29") (pinfunction "GND_29") (pintype "passive"))
      (node (ref "IC1") (pin "3") (pinfunction "AGND_1_3") (pintype "passive"))
      (node (ref "IC1") (pin "48") (pinfunction "AGND_6_48") (pintype "passive"))
      (node (ref "IC1") (pin "9") (pinfunction "AGND_2_9") (pintype "passive"))
      (node (ref "J1") (pin "2") (pinfunction "2_2") (pintype "passive"))
      (node (ref "J10") (pin "1") (pinfunction "1_1") (pintype "passive"))
      (node (ref "J11") (pin "2") (pinfunction "2_2") (pintype "passive"))
      (node (ref "J13") (pin "1") (pinfunction "1_1") (pintype "passive"))
      (node (ref "J15") (pin "2") (pinfunction "2_2") (pintype "passive"))
      (node (ref "J17") (pin "8") (pinfunction "8_8") (pintype "passive"))
      (node (ref "J17") (pin "MH1") (pinfunction "MH1_MH1") (pintype "passive"))
      (node (ref "J17") (pin "MH2") (pinfunction "MH2_MH2") (pintype "passive"))
      (node (ref "J2") (pin "3") (pinfunction "3_3") (pintype "passive"))
      (node (ref "J3") (pin "3") (pinfunction "3_3") (pintype "passive"))
      (node (ref "J4") (pin "1") (pinfunction "1_1") (pintype "passive"))
      (node (ref "J5") (pin "1") (pinfunction "1_1") (pintype "passive"))
      (node (ref "J6") (pin "1") (pinfunction "1_1") (pintype "passive"))
      (node (ref "J7") (pin "1") (pinfunction "1_1") (pintype "passive"))
      (node (ref "J8") (pin "1") (pinfunction "1_1") (pintype "passive"))
      (node (ref "J9") (pin "1") (pinfunction "1_1") (pintype "passive"))
      (node (ref "LED1") (pin "1") (pinfunction "K_1") (pintype "passive"))
      (node (ref "O1") (pin "3") (pinfunction "E_3") (pintype "passive"))
      (node (ref "O2") (pin "3") (pinfunction "E_3") (pintype "passive"))
      (node (ref "O3") (pin "3") (pinfunction "E_3") (pintype "passive"))
      (node (ref "O4") (pin "3") (pinfunction "E_3") (pintype "passive"))
      (node (ref "Q1") (pin "2") (pinfunction "E_2") (pintype "passive"))
      (node (ref "Q2") (pin "2") (pinfunction "E_2") (pintype "passive"))
      (node (ref "Q3") (pin "2") (pinfunction "E_2") (pintype "passive"))
      (node (ref "Q4") (pin "2") (pinfunction "E_2") (pintype "passive"))
      (node (ref "Q5") (pin "2") (pinfunction "E_2") (pintype "passive"))
      (node (ref "Q6") (pin "2") (pinfunction "E_2") (pintype "passive"))
      (node (ref "Q7") (pin "2") (pinfunction "E_2") (pintype "passive"))
      (node (ref "Q8") (pin "2") (pinfunction "E_2") (pintype "passive"))
      (node (ref "R10") (pin "1") (pinfunction "1_1") (pintype "passive"))
      (node (ref "R16") (pin "1") (pinfunction "1_1") (pintype "passive"))
      (node (ref "R17") (pin "1") (pinfunction "1_1") (pintype "passive"))
      (node (ref "R18") (pin "1") (pinfunction "1_1") (pintype "passive"))
      (node (ref "R19") (pin "1") (pinfunction "1_1") (pintype "passive"))
      (node (ref "R24") (pin "1") (pinfunction "1_1") (pintype "passive"))
      (node (ref "R26") (pin "1") (pinfunction "1_1") (pintype "passive"))
      (node (ref "R29") (pin "1") (pinfunction "1_1") (pintype "passive"))
      (node (ref "R30") (pin "1") (pinfunction "1_1") (pintype "passive"))
      (node (ref "R32") (pin "1") (pinfunction "1_1") (pintype "passive"))
      (node (ref "R33") (pin "2") (pinfunction "2_2") (pintype "passive"))
      (node (ref "R38") (pin "1") (pinfunction "1_1") (pintype "passive"))
      (node (ref "R40") (pin "1") (pinfunction "1_1") (pintype "passive"))
      (node (ref "R41") (pin "2") (pinfunction "2_2") (pintype "passive"))
      (node (ref "R44") (pin "1") (pinfunction "1_1") (pintype "passive"))
      (node (ref "R45") (pin "1") (pinfunction "1_1") (pintype "passive"))
      (node (ref "R47") (pin "1") (pinfunction "1_1") (pintype "passive"))
      (node (ref "R51") (pin "3") (pinfunction "CW_3") (pintype "passive"))
      (node (ref "R53") (pin "1") (pinfunction "1_1") (pintype "passive"))
      (node (ref "R54") (pin "1") (pinfunction "1_1") (pintype "passive"))
      (node (ref "R56") (pin "1") (pinfunction "1_1") (pintype "passive"))
      (node (ref "R57") (pin "1") (pinfunction "1_1") (pintype "passive"))
      (node (ref "R58") (pin "1") (pinfunction "1_1") (pintype "passive"))
      (node (ref "R59") (pin "1") (pinfunction "1_1") (pintype "passive"))
      (node (ref "R60") (pin "1") (pinfunction "1_1") (pintype "passive"))
      (node (ref "R61") (pin "1") (pinfunction "1_1") (pintype "passive"))
      (node (ref "R62") (pin "1") (pinfunction "1_1") (pintype "passive"))
      (node (ref "R68") (pin "1") (pinfunction "1_1") (pintype "passive"))
      (node (ref "R70") (pin "1") (pinfunction "1_1") (pintype "passive"))
      (node (ref "R73") (pin "1") (pinfunction "1_1") (pintype "passive"))
      (node (ref "R78") (pin "3") (pinfunction "CW_3") (pintype "passive"))
      (node (ref "R85") (pin "1") (pinfunction "1_1") (pintype "passive"))
      (node (ref "U1") (pin "3") (pinfunction "GROUND_3") (pintype "passive"))
      (node (ref "U1") (pin "5") (pinfunction "~{ON}/OFF_5") (pintype "passive"))
      (node (ref "U1") (pin "6") (pinfunction "GND_6") (pintype "passive"))
      (node (ref "U2") (pin "5") (pinfunction "GND_5") (pintype "power_in"))
      (node (ref "U3") (pin "1") (pinfunction "GND_1") (pintype "power_in"))
      (node (ref "U4") (pin "23") (pinfunction "VSS_23") (pintype "power_in"))
      (node (ref "U4") (pin "35") (pinfunction "VSS_35") (pintype "power_in"))
      (node (ref "U4") (pin "44") (pinfunction "BOOT0_44") (pintype "input"))
      (node (ref "U4") (pin "47") (pinfunction "VSS_47") (pintype "power_in"))
      (node (ref "U4") (pin "8") (pinfunction "VSSA_8") (pintype "power_in"))
      (node (ref "U5") (pin "4") (pinfunction "V-_4") (pintype "power_in"))
    )
    (net (code "42") (name "Net-(C41-Pad1)") (class "Default")
      (node (ref "C41") (pin "1") (pinfunction "1_1") (pintype "passive"))
      (node (ref "J17") (pin "4") (pinfunction "4_4") (pintype "passive"))
      (node (ref "R74") (pin "1") (pinfunction "1_1") (pintype "passive"))
    )
    (net (code "43") (name "Net-(C42-Pad1)") (class "Default")
      (node (ref "C42") (pin "1") (pinfunction "1_1") (pintype "passive"))
      (node (ref "R81") (pin "2") (pinfunction "2_2") (pintype "passive"))
      (node (ref "R86") (pin "2") (pinfunction "2_2") (pintype "passive"))
    )
    (net (code "44") (name "Net-(C42-Pad2)") (class "Default")
      (node (ref "C42") (pin "2") (pinfunction "2_2") (pintype "passive"))
      (node (ref "J17") (pin "3") (pinfunction "3_3") (pintype "passive"))
    )
    (net (code "45") (name "Net-(C43-Pad1)") (class "Default")
      (node (ref "C43") (pin "1") (pinfunction "1_1") (pintype "passive"))
      (node (ref "R83") (pin "2") (pinfunction "2_2") (pintype "passive"))
      (node (ref "R87") (pin "2") (pinfunction "2_2") (pintype "passive"))
    )
    (net (code "46") (name "Net-(C43-Pad2)") (class "Default")
      (node (ref "C43") (pin "2") (pinfunction "2_2") (pintype "passive"))
      (node (ref "J17") (pin "6") (pinfunction "6_6") (pintype "passive"))
    )
    (net (code "47") (name "Net-(C44-Pad1)") (class "Default")
      (node (ref "C44") (pin "1") (pinfunction "1_1") (pintype "passive"))
      (node (ref "J17") (pin "5") (pinfunction "5_5") (pintype "passive"))
      (node (ref "R86") (pin "1") (pinfunction "1_1") (pintype "passive"))
      (node (ref "R87") (pin "1") (pinfunction "1_1") (pintype "passive"))
    )
    (net (code "48") (name "Net-(D1-K)") (class "Default")
      (node (ref "D1") (pin "1") (pinfunction "K_1") (pintype "passive"))
      (node (ref "L1") (pin "1") (pinfunction "1_1") (pintype "passive"))
      (node (ref "U1") (pin "2") (pinfunction "OUTPUT_2") (pintype "passive"))
    )
    (net (code "49") (name "Net-(D8-A)") (class "Default")
      (node (ref "D8") (pin "2") (pinfunction "A_2") (pintype "passive"))
      (node (ref "K1") (pin "1") (pinfunction "COIL_1_1") (pintype "passive"))
      (node (ref "LED8") (pin "1") (pinfunction "K_1") (pintype "passive"))
      (node (ref "Q5") (pin "3") (pinfunction "C_3") (pintype "passive"))
    )
    (net (code "50") (name "Net-(D11-A)") (class "Default")
      (node (ref "D11") (pin "2") (pinfunction "A_2") (pintype "passive"))
      (node (ref "K2") (pin "1") (pinfunction "COIL_1_1") (pintype "passive"))
      (node (ref "LED9") (pin "1") (pinfunction "K_1") (pintype "passive"))
      (node (ref "Q6") (pin "3") (pinfunction "C_3") (pintype "passive"))
    )
    (net (code "51") (name "Net-(D12-A)") (class "Default")
      (node (ref "D12") (pin "2") (pinfunction "A_2") (pintype "passive"))
      (node (ref "K3") (pin "1") (pinfunction "COIL_1_1") (pintype "passive"))
      (node (ref "LED10") (pin "1") (pinfunction "K_1") (pintype "passive"))
      (node (ref "Q7") (pin "3") (pinfunction "C_3") (pintype "passive"))
    )
    (net (code "52") (name "Net-(D13-A)") (class "Default")
      (node (ref "D13") (pin "2") (pinfunction "A_2") (pintype "passive"))
      (node (ref "K4") (pin "1") (pinfunction "COIL_1_1") (pintype "passive"))
      (node (ref "LED11") (pin "1") (pinfunction "K_1") (pintype "passive"))
      (node (ref "Q8") (pin "3") (pinfunction "C_3") (pintype "passive"))
    )
    (net (code "53") (name "Net-(IC1-1V2O)") (class "Default")
      (node (ref "C19") (pin "2") (pinfunction "2_2") (pintype "passive"))
      (node (ref "IC1") (pin "22") (pinfunction "1V2O_22") (pintype "passive"))
    )
    (net (code "54") (name "Net-(IC1-EXRES1)") (class "Default")
      (node (ref "IC1") (pin "10") (pinfunction "EXRES1_10") (pintype "passive"))
      (node (ref "R41") (pin "1") (pinfunction "1_1") (pintype "passive"))
    )
    (net (code "55") (name "Net-(IC1-PMODE0)") (class "Default")
      (node (ref "IC1") (pin "45") (pinfunction "PMODE0_45") (pintype "passive"))
      (node (ref "R65") (pin "2") (pinfunction "2_2") (pintype "passive"))
    )
    (net (code "56") (name "Net-(IC1-PMODE1)") (class "Default")
      (node (ref "IC1") (pin "44") (pinfunction "PMODE1_44") (pintype "passive"))
      (node (ref "R64") (pin "2") (pinfunction "2_2") (pintype "passive"))
    )
    (net (code "57") (name "Net-(IC1-PMODE2)") (class "Default")
      (node (ref "IC1") (pin "43") (pinfunction "PMODE2_43") (pintype "passive"))
      (node (ref "R63") (pin "2") (pinfunction "2_2") (pintype "passive"))
    )
    (net (code "58") (name "Net-(IC1-RSVD_1)") (class "Default")
      (node (ref "IC1") (pin "23") (pinfunction "RSVD_1_23") (pintype "passive"))
      (node (ref "R33") (pin "1") (pinfunction "1_1") (pintype "passive"))
    )
    (net (code "59") (name "Net-(IC1-RSVD_2)") (class "Default")
      (node (ref "IC1") (pin "38") (pinfunction "RSVD_2_38") (pintype "passive"))
      (node (ref "R56") (pin "2") (pinfunction "2_2") (pintype "passive"))
    )
    (net (code "60") (name "Net-(IC1-RSVD_3)") (class "Default")
      (node (ref "IC1") (pin "39") (pinfunction "RSVD_3_39") (pintype "passive"))
      (node (ref "R57") (pin "2") (pinfunction "2_2") (pintype "passive"))
    )
    (net (code "61") (name "Net-(IC1-RSVD_4)") (class "Default")
      (node (ref "IC1") (pin "40") (pinfunction "RSVD_4_40") (pintype "passive"))
      (node (ref "R58") (pin "2") (pinfunction "2_2") (pintype "passive"))
    )
    (net (code "62") (name "Net-(IC1-RSVD_5)") (class "Default")
      (node (ref "IC1") (pin "41") (pinfunction "RSVD_5_41") (pintype "passive"))
      (node (ref "R59") (pin "2") (pinfunction "2_2") (pintype "passive"))
    )
    (net (code "63") (name "Net-(IC1-RSVD_6)") (class "Default")
      (node (ref "IC1") (pin "42") (pinfunction "RSVD_6_42") (pintype "passive"))
      (node (ref "R60") (pin "2") (pinfunction "2_2") (pintype "passive"))
    )
    (net (code "64") (name "Net-(IC1-TOCAP)") (class "Default")
      (node (ref "C20") (pin "2") (pinfunction "2_2") (pintype "passive"))
      (node (ref "IC1") (pin "20") (pinfunction "TOCAP_20") (pintype "passive"))
    )
    (net (code "65") (name "Net-(J2-Pad1)") (class "Default")
      (node (ref "J2") (pin "1") (pinfunction "1_1") (pintype "passive"))
      (node (ref "R9") (pin "2") (pinfunction "2_2") (pintype "passive"))
    )
    (net (code "66") (name "Net-(J2-Pad2)") (class "Default")
      (node (ref "J2") (pin "2") (pinfunction "2_2") (pintype "passive"))
      (node (ref "R5") (pin "2") (pinfunction "2_2") (pintype "passive"))
    )
    (net (code "67") (name "Net-(J4-Pad2)") (class "Default")
      (node (ref "J4") (pin "2") (pinfunction "2_2") (pintype "passive"))
      (node (ref "R15") (pin "1") (pinfunction "1_1") (pintype "passive"))
    )
    (net (code "68") (name "Net-(J5-Pad2)") (class "Default")
      (node (ref "J5") (pin "2") (pinfunction "2_2") (pintype "passive"))
      (node (ref "P1") (pin "1") (pinfunction "1_1") (pintype "passive"))
      (node (ref "R13") (pin "1") (pinfunction "1_1") (pintype "passive"))
      (node (ref "R14") (pin "1") (pinfunction "1_1") (pintype "passive"))
    )
    (net (code "69") (name "Net-(J6-Pad2)") (class "Default")
      (node (ref "J6") (pin "2") (pinfunction "2_2") (pintype "passive"))
      (node (ref "R22") (pin "1") (pinfunction "1_1") (pintype "passive"))
    )
    (net (code "70") (name "Net-(J7-Pad2)") (class "Default")
      (node (ref "J7") (pin "2") (pinfunction "2_2") (pintype "passive"))
      (node (ref "P2") (pin "1") (pinfunction "1_1") (pintype "passive"))
      (node (ref "R23") (pin "1") (pinfunction "1_1") (pintype "passive"))
      (node (ref "R25") (pin "1") (pinfunction "1_1") (pintype "passive"))
    )
    (net (code "71") (name "Net-(J8-Pad2)") (class "Default")
      (node (ref "J8") (pin "2") (pinfunction "2_2") (pintype "passive"))
      (node (ref "R31") (pin "1") (pinfunction "1_1") (pintype "passive"))
    )
    (net (code "72") (name "Net-(J9-Pad2)") (class "Default")
      (node (ref "J9") (pin "2") (pinfunction "2_2") (pintype "passive"))
      (node (ref "P3") (pin "1") (pinfunction "1_1") (pintype "passive"))
      (node (ref "R34") (pin "1") (pinfunction "1_1") (pintype "passive"))
      (node (ref "R37") (pin "1") (pinfunction "1_1") (pintype "passive"))
    )
    (net (code "73") (name "Net-(J10-Pad2)") (class "Default")
      (node (ref "J10") (pin "2") (pinfunction "2_2") (pintype "passive"))
      (node (ref "R39") (pin "1") (pinfunction "1_1") (pintype "passive"))
    )
    (net (code "74") (name "Net-(J13-Pad2)") (class "Default")
      (node (ref "J13") (pin "2") (pinfunction "2_2") (pintype "passive"))
      (node (ref "P4") (pin "1") (pinfunction "1_1") (pintype "passive"))
      (node (ref "R49") (pin "1") (pinfunction "1_1") (pintype "passive"))
      (node (ref "R52") (pin "1") (pinfunction "1_1") (pintype "passive"))
    )
    (net (code "75") (name "Net-(J17-Pad1)") (class "Default")
      (node (ref "J17") (pin "1") (pinfunction "1_1") (pintype "passive"))
      (node (ref "R76") (pin "1") (pinfunction "1_1") (pintype "passive"))
      (node (ref "R77") (pin "2") (pinfunction "2_2") (pintype "passive"))
    )
    (net (code "76") (name "Net-(J17-Pad2)") (class "Default")
      (node (ref "J17") (pin "2") (pinfunction "2_2") (pintype "passive"))
      (node (ref "R75") (pin "1") (pinfunction "1_1") (pintype "passive"))
      (node (ref "R79") (pin "2") (pinfunction "2_2") (pintype "passive"))
    )
    (net (code "77") (name "Net-(J17-Pad10)") (class "Default")
      (node (ref "J17") (pin "10") (pinfunction "10_10") (pintype "passive"))
      (node (ref "R80") (pin "1") (pinfunction "1_1") (pintype "passive"))
    )
    (net (code "78") (name "Net-(J17-Pad11)") (class "Default")
      (node (ref "J17") (pin "11") (pinfunction "11_11") (pintype "passive"))
      (node (ref "R82") (pin "1") (pinfunction "1_1") (pintype "passive"))
    )
    (net (code "79") (name "Net-(K1-COM)") (class "Default")
      (node (ref "J12") (pin "2") (pinfunction "2_2") (pintype "passive"))
      (node (ref "K1") (pin "5") (pinfunction "COM_5") (pintype "passive"))
    )
    (net (code "80") (name "Net-(K1-NC)") (class "Default")
      (node (ref "J12") (pin "1") (pinfunction "1_1") (pintype "passive"))
      (node (ref "K1") (pin "2") (pinfunction "NC_2") (pintype "passive"))
    )
    (net (code "81") (name "Net-(K1-NO)") (class "Default")
      (node (ref "J12") (pin "3") (pinfunction "3_3") (pintype "passive"))
      (node (ref "K1") (pin "3") (pinfunction "NO_3") (pintype "passive"))
    )
    (net (code "82") (name "Net-(K2-COM)") (class "Default")
      (node (ref "J14") (pin "2") (pinfunction "2_2") (pintype "passive"))
      (node (ref "K2") (pin "5") (pinfunction "COM_5") (pintype "passive"))
    )
    (net (code "83") (name "Net-(K2-NC)") (class "Default")
      (node (ref "J14") (pin "1") (pinfunction "1_1") (pintype "passive"))
      (node (ref "K2") (pin "2") (pinfunction "NC_2") (pintype "passive"))
    )
    (net (code "84") (name "Net-(K2-NO)") (class "Default")
      (node (ref "J14") (pin "3") (pinfunction "3_3") (pintype "passive"))
      (node (ref "K2") (pin "3") (pinfunction "NO_3") (pintype "passive"))
    )
    (net (code "85") (name "Net-(K3-COM)") (class "Default")
      (node (ref "J16") (pin "2") (pinfunction "2_2") (pintype "passive"))
      (node (ref "K3") (pin "5") (pinfunction "COM_5") (pintype "passive"))
    )
    (net (code "86") (name "Net-(K3-NC)") (class "Default")
      (node (ref "J16") (pin "1") (pinfunction "1_1") (pintype "passive"))
      (node (ref "K3") (pin "2") (pinfunction "NC_2") (pintype "passive"))
    )
    (net (code "87") (name "Net-(K3-NO)") (class "Default")
      (node (ref "J16") (pin "3") (pinfunction "3_3") (pintype "passive"))
      (node (ref "K3") (pin "3") (pinfunction "NO_3") (pintype "passive"))
    )
    (net (code "88") (name "Net-(K4-COM)") (class "Default")
      (node (ref "J18") (pin "2") (pinfunction "2_2") (pintype "passive"))
      (node (ref "K4") (pin "5") (pinfunction "COM_5") (pintype "passive"))
    )
    (net (code "89") (name "Net-(K4-NC)") (class "Default")
      (node (ref "J18") (pin "1") (pinfunction "1_1") (pintype "passive"))
      (node (ref "K4") (pin "2") (pinfunction "NC_2") (pintype "passive"))
    )
    (net (code "90") (name "Net-(K4-NO)") (class "Default")
      (node (ref "J18") (pin "3") (pinfunction "3_3") (pintype "passive"))
      (node (ref "K4") (pin "3") (pinfunction "NO_3") (pintype "passive"))
    )
    (net (code "91") (name "Net-(LED1-A)") (class "Default")
      (node (ref "LED1") (pin "2") (pinfunction "A_2") (pintype "passive"))
      (node (ref "R1") (pin "1") (pinfunction "1_1") (pintype "passive"))
    )
    (net (code "92") (name "Net-(LED2-A)") (class "Default")
      (node (ref "LED2") (pin "2") (pinfunction "A_2") (pintype "passive"))
      (node (ref "R3") (pin "1") (pinfunction "1_1") (pintype "passive"))
    )
    (net (code "93") (name "Net-(LED3-A)") (class "Default")
      (node (ref "LED3") (pin "2") (pinfunction "A_2") (pintype "passive"))
      (node (ref "R2") (pin "1") (pinfunction "1_1") (pintype "passive"))
    )
    (net (code "94") (name "Net-(LED4-A)") (class "Default")
      (node (ref "LED4") (pin "2") (pinfunction "A_2") (pintype "passive"))
      (node (ref "R88") (pin "2") (pinfunction "2_2") (pintype "passive"))
    )
    (net (code "95") (name "Net-(LED5-A)") (class "Default")
      (node (ref "LED5") (pin "2") (pinfunction "A_2") (pintype "passive"))
      (node (ref "R89") (pin "2") (pinfunction "2_2") (pintype "passive"))
    )
    (net (code "96") (name "Net-(LED6-A)") (class "Default")
      (node (ref "LED6") (pin "2") (pinfunction "A_2") (pintype "passive"))
      (node (ref "R90") (pin "2") (pinfunction "2_2") (pintype "passive"))
    )
    (net (code "97") (name "Net-(LED7-A)") (class "Default")
      (node (ref "LED7") (pin "2") (pinfunction "A_2") (pintype "passive"))
      (node (ref "R91") (pin "2") (pinfunction "2_2") (pintype "passive"))
    )
    (net (code "98") (name "Net-(LED8-A)") (class "Default")
      (node (ref "LED8") (pin "2") (pinfunction "A_2") (pintype "passive"))
      (node (ref "R92") (pin "2") (pinfunction "2_2") (pintype "passive"))
    )
    (net (code "99") (name "Net-(LED9-A)") (class "Default")
      (node (ref "LED9") (pin "2") (pinfunction "A_2") (pintype "passive"))
      (node (ref "R93") (pin "2") (pinfunction "2_2") (pintype "passive"))
    )
    (net (code "100") (name "Net-(LED10-A)") (class "Default")
      (node (ref "LED10") (pin "2") (pinfunction "A_2") (pintype "passive"))
      (node (ref "R94") (pin "2") (pinfunction "2_2") (pintype "passive"))
    )
    (net (code "101") (name "Net-(LED11-A)") (class "Default")
      (node (ref "LED11") (pin "2") (pinfunction "A_2") (pintype "passive"))
      (node (ref "R95") (pin "2") (pinfunction "2_2") (pintype "passive"))
    )
    (net (code "102") (name "Net-(O1-A)") (class "Default")
      (node (ref "O1") (pin "1") (pinfunction "A_1") (pintype "passive"))
      (node (ref "R11") (pin "1") (pinfunction "1_1") (pintype "passive"))
    )
    (net (code "103") (name "Net-(O2-A)") (class "Default")
      (node (ref "O2") (pin "1") (pinfunction "A_1") (pintype "passive"))
      (node (ref "R21") (pin "1") (pinfunction "1_1") (pintype "passive"))
    )
    (net (code "104") (name "Net-(O3-A)") (class "Default")
      (node (ref "O3") (pin "1") (pinfunction "A_1") (pintype "passive"))
      (node (ref "R27") (pin "1") (pinfunction "1_1") (pintype "passive"))
    )
    (net (code "105") (name "Net-(O4-A)") (class "Default")
      (node (ref "O4") (pin "1") (pinfunction "A_1") (pintype "passive"))
      (node (ref "R35") (pin "1") (pinfunction "1_1") (pintype "passive"))
    )
    (net (code "106") (name "Net-(P1-Pad2)") (class "Default")
      (node (ref "P1") (pin "2") (pinfunction "2_2") (pintype "passive"))
      (node (ref "R18") (pin "2") (pinfunction "2_2") (pintype "passive"))
      (node (ref "R19") (pin "2") (pinfunction "2_2") (pintype "passive"))
    )
    (net (code "107") (name "Net-(P2-Pad2)") (class "Default")
      (node (ref "P2") (pin "2") (pinfunction "2_2") (pintype "passive"))
      (node (ref "R29") (pin "2") (pinfunction "2_2") (pintype "passive"))
      (node (ref "R30") (pin "2") (pinfunction "2_2") (pintype "passive"))
    )
    (net (code "108") (name "Net-(P3-Pad2)") (class "Default")
      (node (ref "P3") (pin "2") (pinfunction "2_2") (pintype "passive"))
      (node (ref "R44") (pin "2") (pinfunction "2_2") (pintype "passive"))
      (node (ref "R45") (pin "2") (pinfunction "2_2") (pintype "passive"))
    )
    (net (code "109") (name "Net-(P4-Pad2)") (class "Default")
      (node (ref "P4") (pin "2") (pinfunction "2_2") (pintype "passive"))
      (node (ref "R61") (pin "2") (pinfunction "2_2") (pintype "passive"))
      (node (ref "R62") (pin "2") (pinfunction "2_2") (pintype "passive"))
    )
    (net (code "110") (name "Net-(Q1-B)") (class "Default")
      (node (ref "Q1") (pin "1") (pinfunction "B_1") (pintype "passive"))
      (node (ref "R15") (pin "2") (pinfunction "2_2") (pintype "passive"))
      (node (ref "R16") (pin "2") (pinfunction "2_2") (pintype "passive"))
    )
    (net (code "111") (name "Net-(Q1-C)") (class "Default")
      (node (ref "O1") (pin "2") (pinfunction "C_2") (pintype "passive"))
      (node (ref "Q1") (pin "3") (pinfunction "C_3") (pintype "passive"))
    )
    (net (code "112") (name "Net-(Q2-B)") (class "Default")
      (node (ref "Q2") (pin "1") (pinfunction "B_1") (pintype "passive"))
      (node (ref "R22") (pin "2") (pinfunction "2_2") (pintype "passive"))
      (node (ref "R24") (pin "2") (pinfunction "2_2") (pintype "passive"))
    )
    (net (code "113") (name "Net-(Q2-C)") (class "Default")
      (node (ref "O2") (pin "2") (pinfunction "C_2") (pintype "passive"))
      (node (ref "Q2") (pin "3") (pinfunction "C_3") (pintype "passive"))
    )
    (net (code "114") (name "Net-(Q3-B)") (class "Default")
      (node (ref "Q3") (pin "1") (pinfunction "B_1") (pintype "passive"))
      (node (ref "R31") (pin "2") (pinfunction "2_2") (pintype "passive"))
      (node (ref "R32") (pin "2") (pinfunction "2_2") (pintype "passive"))
    )
    (net (code "115") (name "Net-(Q3-C)") (class "Default")
      (node (ref "O3") (pin "2") (pinfunction "C_2") (pintype "passive"))
      (node (ref "Q3") (pin "3") (pinfunction "C_3") (pintype "passive"))
    )
    (net (code "116") (name "Net-(Q4-B)") (class "Default")
      (node (ref "Q4") (pin "1") (pinfunction "B_1") (pintype "passive"))
      (node (ref "R39") (pin "2") (pinfunction "2_2") (pintype "passive"))
      (node (ref "R40") (pin "2") (pinfunction "2_2") (pintype "passive"))
    )
    (net (code "117") (name "Net-(Q4-C)") (class "Default")
      (node (ref "O4") (pin "2") (pinfunction "C_2") (pintype "passive"))
      (node (ref "Q4") (pin "3") (pinfunction "C_3") (pintype "passive"))
    )
    (net (code "118") (name "Net-(Q5-B)") (class "Default")
      (node (ref "Q5") (pin "1") (pinfunction "B_1") (pintype "passive"))
      (node (ref "R50") (pin "2") (pinfunction "2_2") (pintype "passive"))
      (node (ref "R53") (pin "2") (pinfunction "2_2") (pintype "passive"))
    )
    (net (code "119") (name "Net-(Q6-B)") (class "Default")
      (node (ref "Q6") (pin "1") (pinfunction "B_1") (pintype "passive"))
      (node (ref "R67") (pin "2") (pinfunction "2_2") (pintype "passive"))
      (node (ref "R68") (pin "2") (pinfunction "2_2") (pintype "passive"))
    )
    (net (code "120") (name "Net-(Q7-B)") (class "Default")
      (node (ref "Q7") (pin "1") (pinfunction "B_1") (pintype "passive"))
      (node (ref "R72") (pin "2") (pinfunction "2_2") (pintype "passive"))
      (node (ref "R73") (pin "2") (pinfunction "2_2") (pintype "passive"))
    )
    (net (code "121") (name "Net-(Q8-B)") (class "Default")
      (node (ref "Q8") (pin "1") (pinfunction "B_1") (pintype "passive"))
      (node (ref "R84") (pin "2") (pinfunction "2_2") (pintype "passive"))
      (node (ref "R85") (pin "2") (pinfunction "2_2") (pintype "passive"))
    )
    (net (code "122") (name "Net-(R51-CCW)") (class "Default")
      (node (ref "R48") (pin "1") (pinfunction "1_1") (pintype "passive"))
      (node (ref "R51") (pin "1") (pinfunction "CCW_1") (pintype "passive"))
      (node (ref "R51") (pin "2") (pinfunction "WIPER_2") (pintype "passive"))
    )
    (net (code "123") (name "Net-(R78-CCW)") (class "Default")
      (node (ref "R71") (pin "1") (pinfunction "1_1") (pintype "passive"))
      (node (ref "R78") (pin "1") (pinfunction "CCW_1") (pintype "passive"))
      (node (ref "R78") (pin "2") (pinfunction "WIPER_2") (pintype "passive"))
    )
    (net (code "124") (name "Net-(U2-A)") (class "Default")
      (node (ref "C3") (pin "2") (pinfunction "2_2") (pintype "passive"))
      (node (ref "R4") (pin "1") (pinfunction "1_1") (pintype "passive"))
      (node (ref "R8") (pin "1") (pinfunction "1_1") (pintype "passive"))
      (node (ref "R9") (pin "1") (pinfunction "1_1") (pintype "passive"))
      (node (ref "U2") (pin "6") (pinfunction "A_6") (pintype "bidirectional"))
    )
    (net (code "125") (name "Net-(U2-B)") (class "Default")
      (node (ref "C5") (pin "1") (pinfunction "1_1") (pintype "passive"))
      (node (ref "R10") (pin "2") (pinfunction "2_2") (pintype "passive"))
      (node (ref "R5") (pin "1") (pinfunction "1_1") (pintype "passive"))
      (node (ref "R8") (pin "2") (pinfunction "2_2") (pintype "passive"))
      (node (ref "U2") (pin "7") (pinfunction "B_7") (pintype "bidirectional"))
    )
    (net (code "126") (name "Net-(U2-RO)") (class "Default")
      (node (ref "R7") (pin "2") (pinfunction "2_2") (pintype "passive"))
      (node (ref "U2") (pin "1") (pinfunction "RO_1") (pintype "output"))
    )
    (net (code "127") (name "Net-(U5A-1OUT)") (class "Default")
      (node (ref "J11") (pin "1") (pinfunction "1_1") (pintype "passive"))
      (node (ref "R46") (pin "2") (pinfunction "2_2") (pintype "passive"))
      (node (ref "U5") (pin "1") (pinfunction "1OUT_1") (pintype "output"))
    )
    (net (code "128") (name "Net-(U5A-IN1-)") (class "Default")
      (node (ref "R46") (pin "1") (pinfunction "1_1") (pintype "passive"))
      (node (ref "R48") (pin "2") (pinfunction "2_2") (pintype "passive"))
      (node (ref "U5") (pin "2") (pinfunction "IN1-_2") (pintype "tri_state"))
    )
    (net (code "129") (name "Net-(U5B-2OUT)") (class "Default")
      (node (ref "J15") (pin "1") (pinfunction "1_1") (pintype "passive"))
      (node (ref "R69") (pin "2") (pinfunction "2_2") (pintype "passive"))
      (node (ref "U5") (pin "7") (pinfunction "2OUT_7") (pintype "output"))
    )
    (net (code "130") (name "Net-(U5B-IN2-)") (class "Default")
      (node (ref "R69") (pin "1") (pinfunction "1_1") (pintype "passive"))
      (node (ref "R71") (pin "2") (pinfunction "2_2") (pintype "passive"))
      (node (ref "U5") (pin "6") (pinfunction "IN2-_6") (pintype "tri_state"))
    )
    (net (code "131") (name "unconnected-(IC1-DNC-Pad7)") (class "Default")
      (node (ref "IC1") (pin "7") (pinfunction "DNC_7") (pintype "passive"))
    )
    (net (code "132") (name "unconnected-(IC1-DUPLED-Pad26)") (class "Default")
      (node (ref "IC1") (pin "26") (pinfunction "DUPLED_26") (pintype "passive"))
    )
    (net (code "133") (name "unconnected-(IC1-NC_1-Pad12)") (class "Default")
      (node (ref "IC1") (pin "12") (pinfunction "NC_1_12") (pintype "passive"))
    )
    (net (code "134") (name "unconnected-(IC1-NC_2-Pad13)") (class "Default")
      (node (ref "IC1") (pin "13") (pinfunction "NC_2_13") (pintype "passive"))
    )
    (net (code "135") (name "unconnected-(IC1-NC_3-Pad46)") (class "Default")
      (node (ref "IC1") (pin "46") (pinfunction "NC_3_46") (pintype "passive"))
    )
    (net (code "136") (name "unconnected-(IC1-NC_4-Pad47)") (class "Default")
      (node (ref "IC1") (pin "47") (pinfunction "NC_4_47") (pintype "passive"))
    )
    (net (code "137") (name "unconnected-(IC1-SPDLED-Pad24)") (class "Default")
      (node (ref "IC1") (pin "24") (pinfunction "SPDLED_24") (pintype "passive"))
    )
    (net (code "138") (name "unconnected-(IC1-VBG-Pad18)") (class "Default")
      (node (ref "IC1") (pin "18") (pinfunction "VBG_18") (pintype "passive"))
    )
    (net (code "139") (name "unconnected-(J17-Pad7)") (class "Default")
      (node (ref "J17") (pin "7") (pinfunction "7_7") (pintype "passive"))
    )
    (net (code "140") (name "unconnected-(U4-PA6-Pad16)") (class "Default")
      (node (ref "U4") (pin "16") (pinfunction "PA6_16") (pintype "bidirectional"))
    )
    (net (code "141") (name "unconnected-(U4-PA7-Pad17)") (class "Default")
      (node (ref "U4") (pin "17") (pinfunction "PA7_17") (pintype "bidirectional"))
    )
    (net (code "142") (name "unconnected-(U4-PA11-Pad32)") (class "Default")
      (node (ref "U4") (pin "32") (pinfunction "PA11_32") (pintype "bidirectional"))
    )
    (net (code "143") (name "unconnected-(U4-PA15-Pad38)") (class "Default")
      (node (ref "U4") (pin "38") (pinfunction "PA15_38") (pintype "bidirectional"))
    )
    (net (code "144") (name "unconnected-(U4-PB0-Pad18)") (class "Default")
      (node (ref "U4") (pin "18") (pinfunction "PB0_18") (pintype "bidirectional"))
    )
    (net (code "145") (name "unconnected-(U4-PB1-Pad19)") (class "Default")
      (node (ref "U4") (pin "19") (pinfunction "PB1_19") (pintype "bidirectional"))
    )
    (net (code "146") (name "unconnected-(U4-PB2-Pad20)") (class "Default")
      (node (ref "U4") (pin "20") (pinfunction "PB2_20") (pintype "bidirectional"))
    )
    (net (code "147") (name "unconnected-(U4-PB3-Pad39)") (class "Default")
      (node (ref "U4") (pin "39") (pinfunction "PB3_39") (pintype "bidirectional"))
    )
    (net (code "148") (name "unconnected-(U4-PB4-Pad40)") (class "Default")
      (node (ref "U4") (pin "40") (pinfunction "PB4_40") (pintype "bidirectional"))
    )
    (net (code "149") (name "unconnected-(U4-PB10-Pad21)") (class "Default")
      (node (ref "U4") (pin "21") (pinfunction "PB10_21") (pintype "bidirectional"))
    )
  )
)
